# F405.net
KiCad netlist of a schematic drawn in Altium Designer
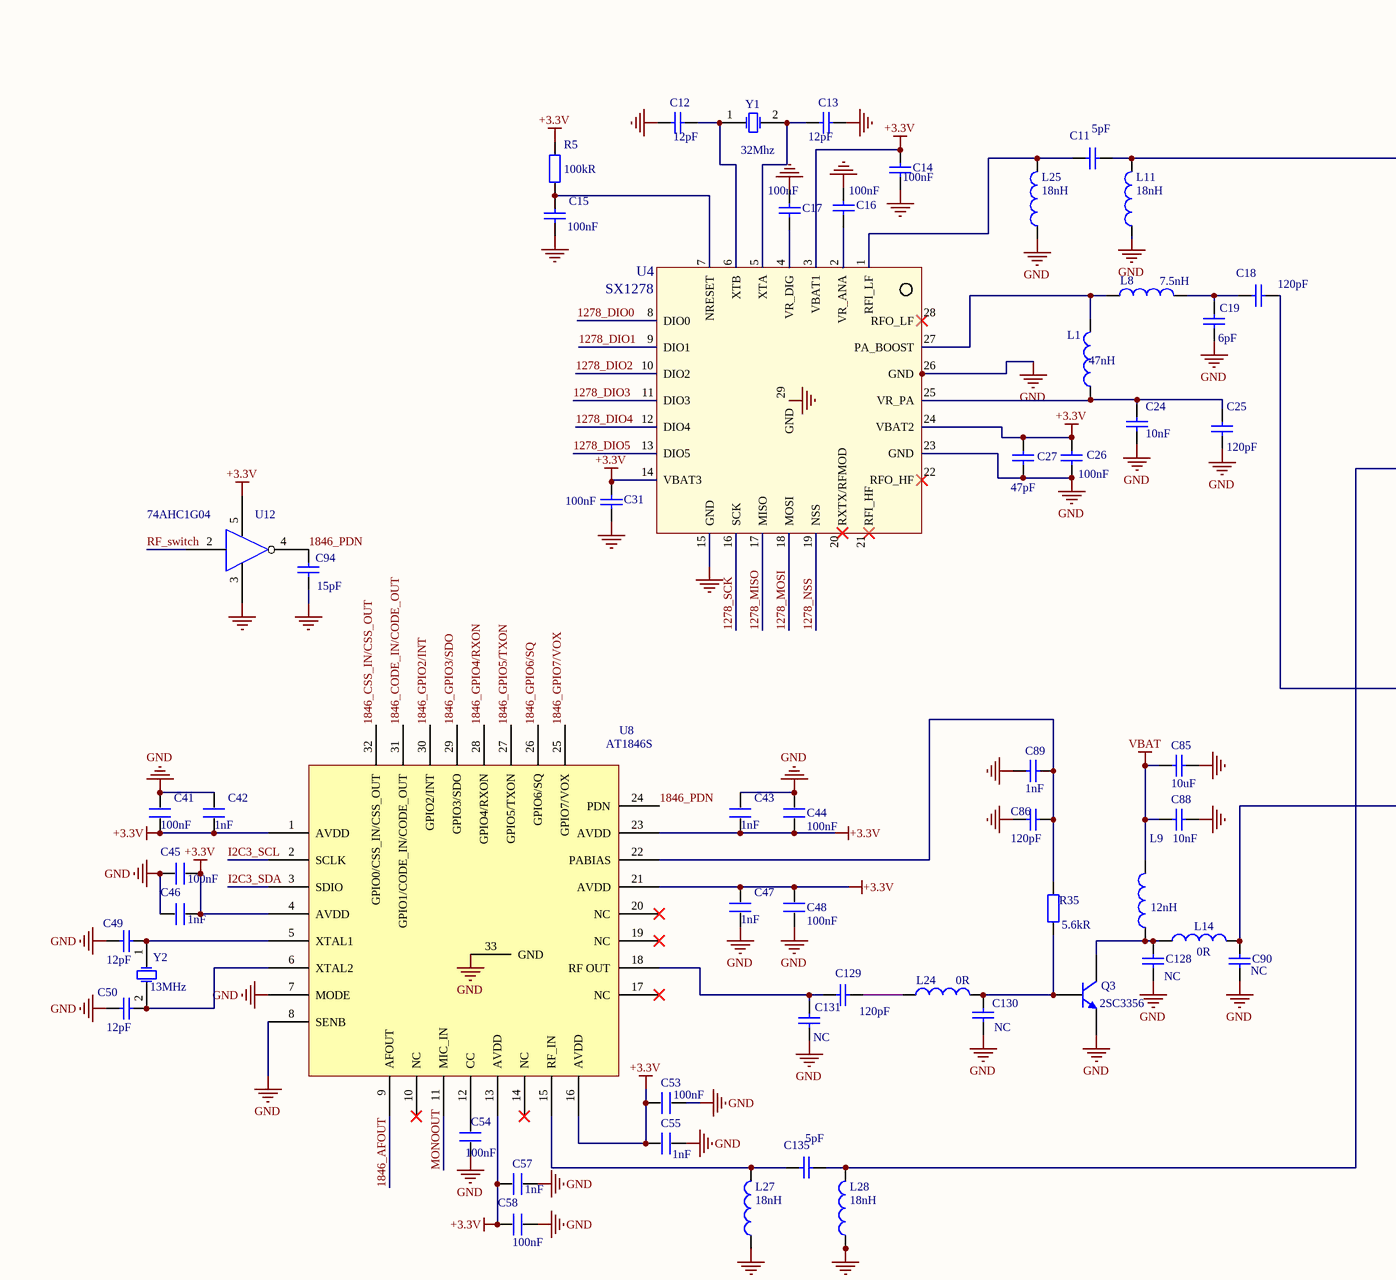
[diagram p0: F405.SchDoc, top left]
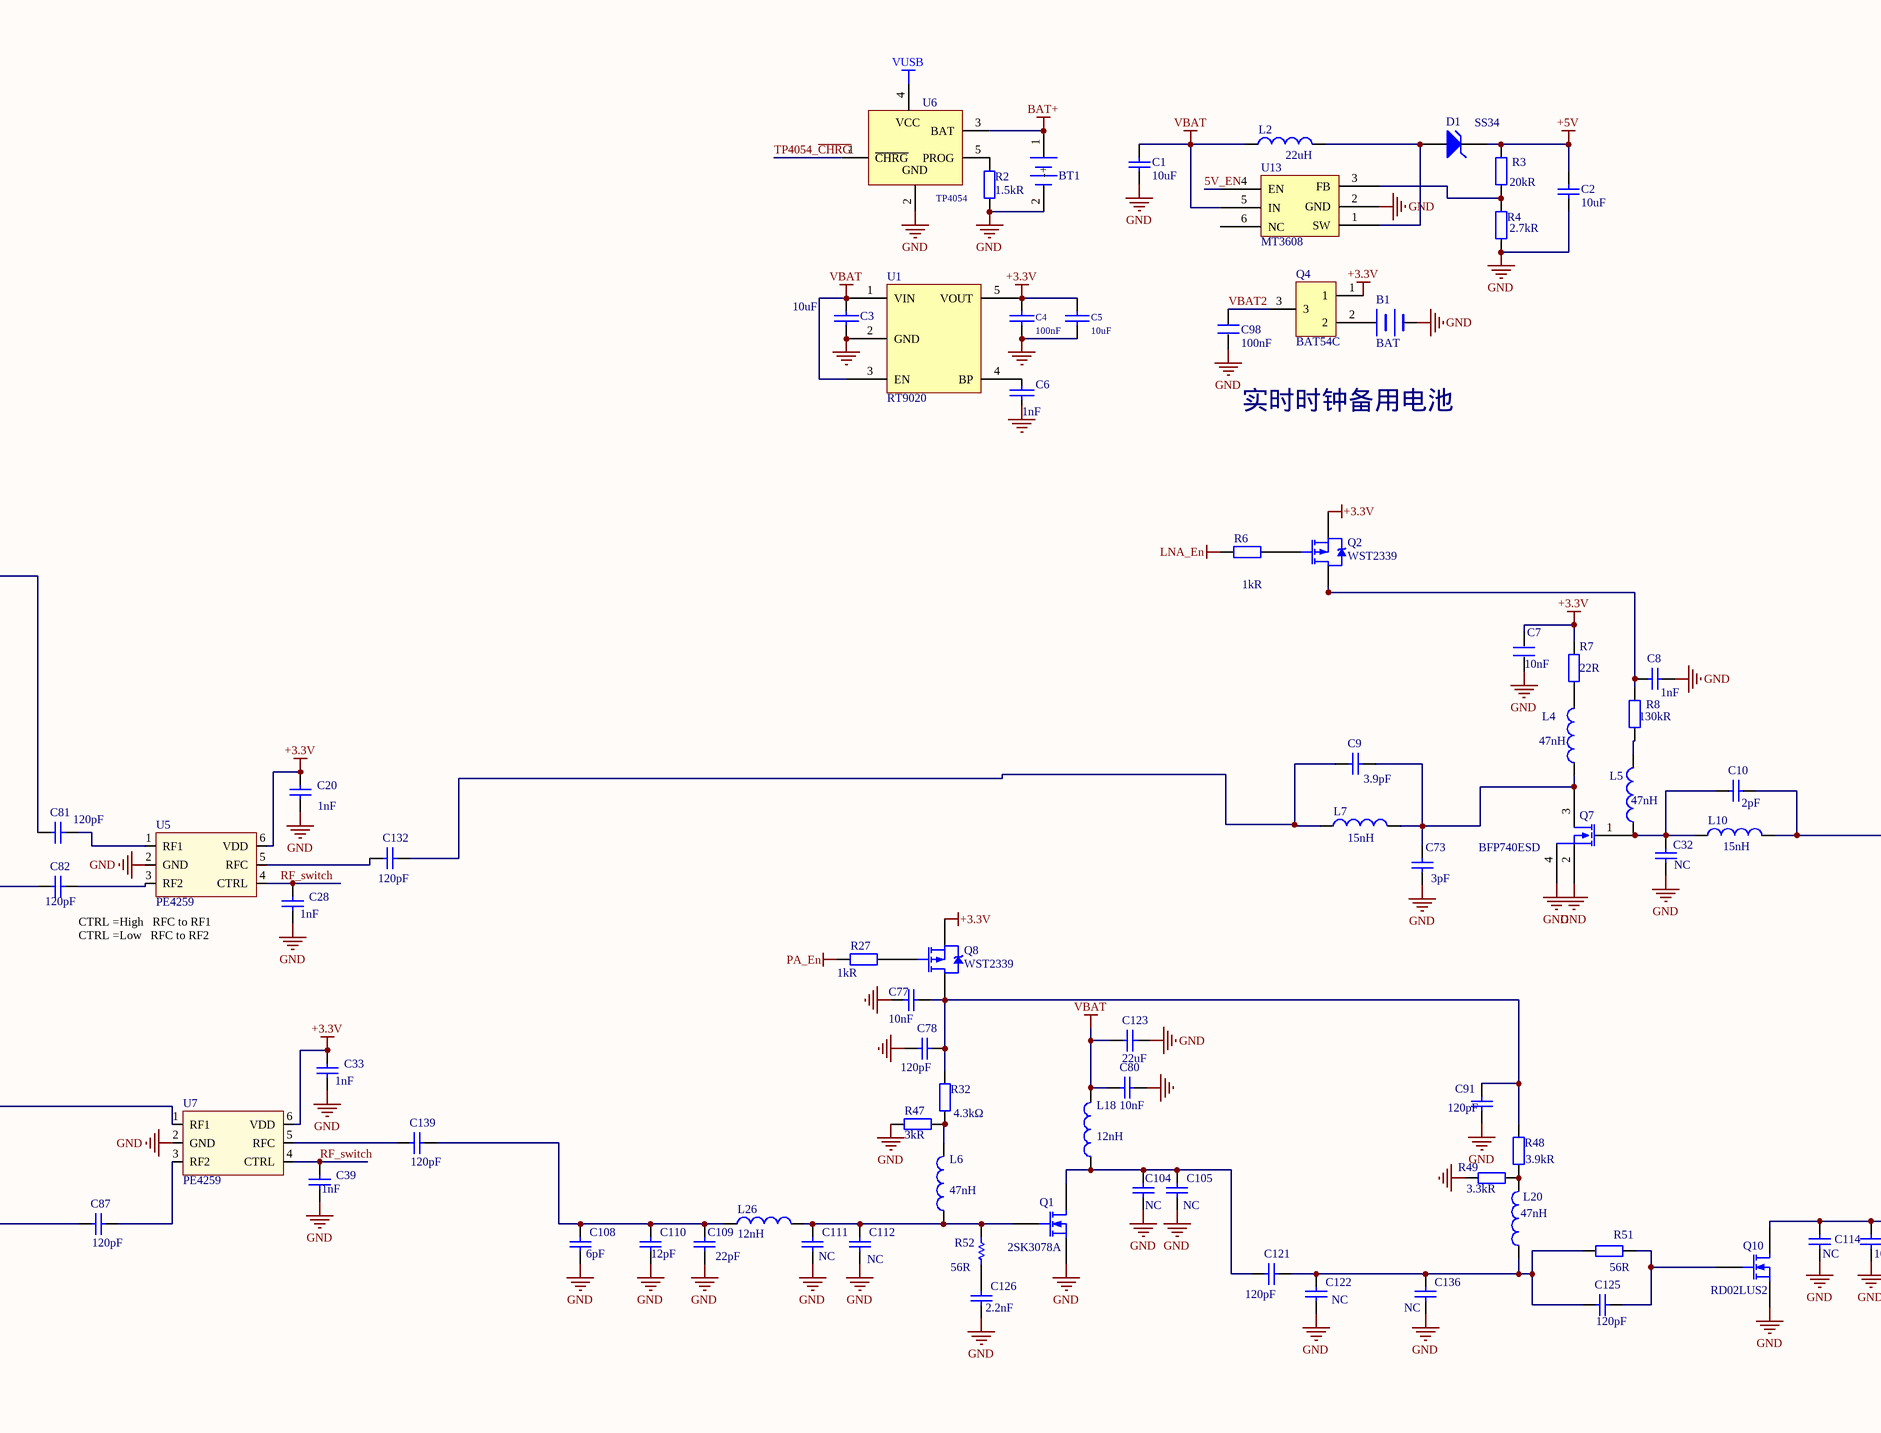
[diagram p1: F405.SchDoc, top middle]
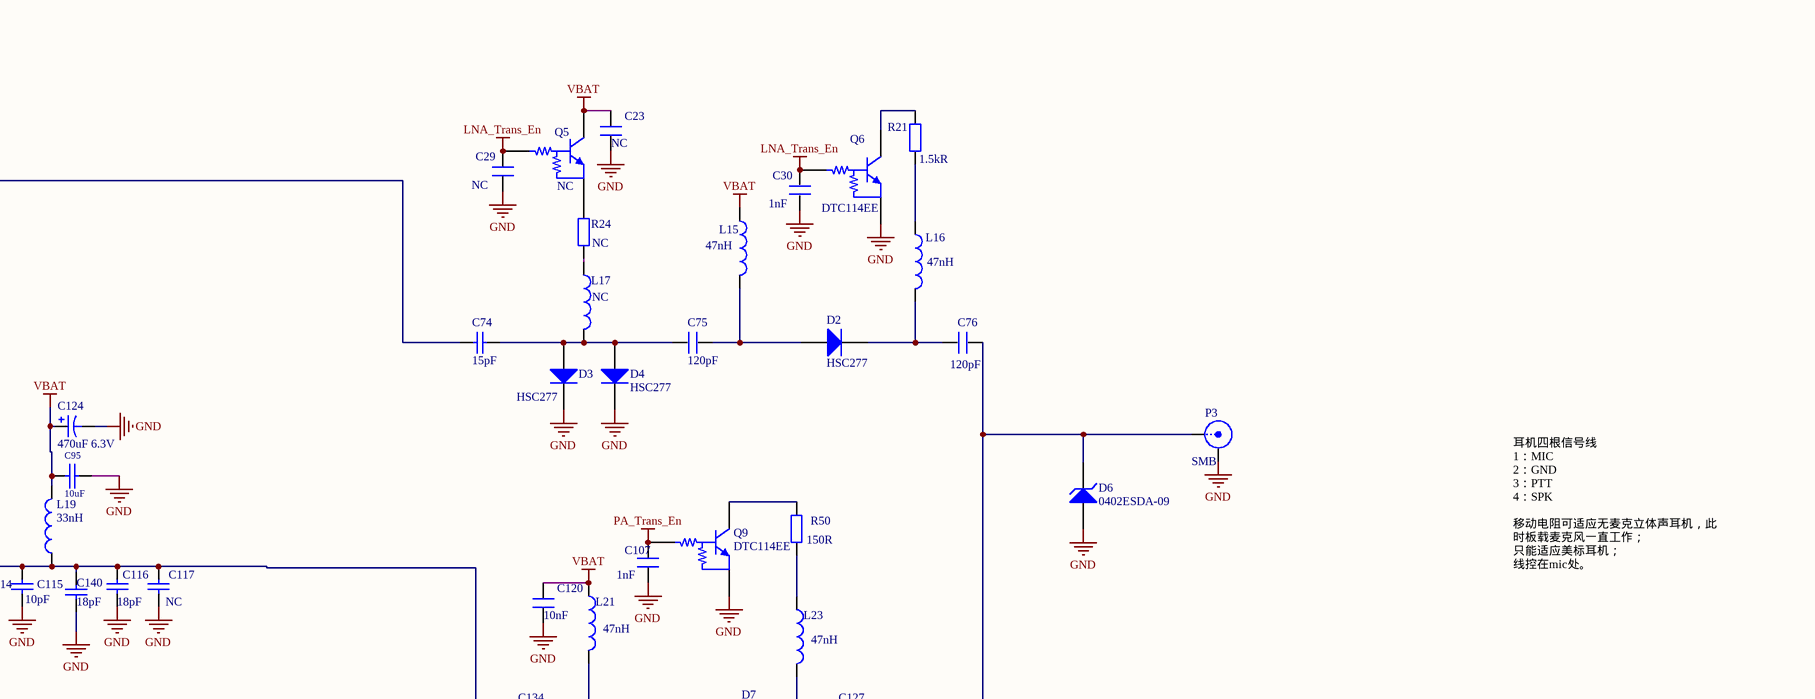
[diagram p2: F405.SchDoc, top right]
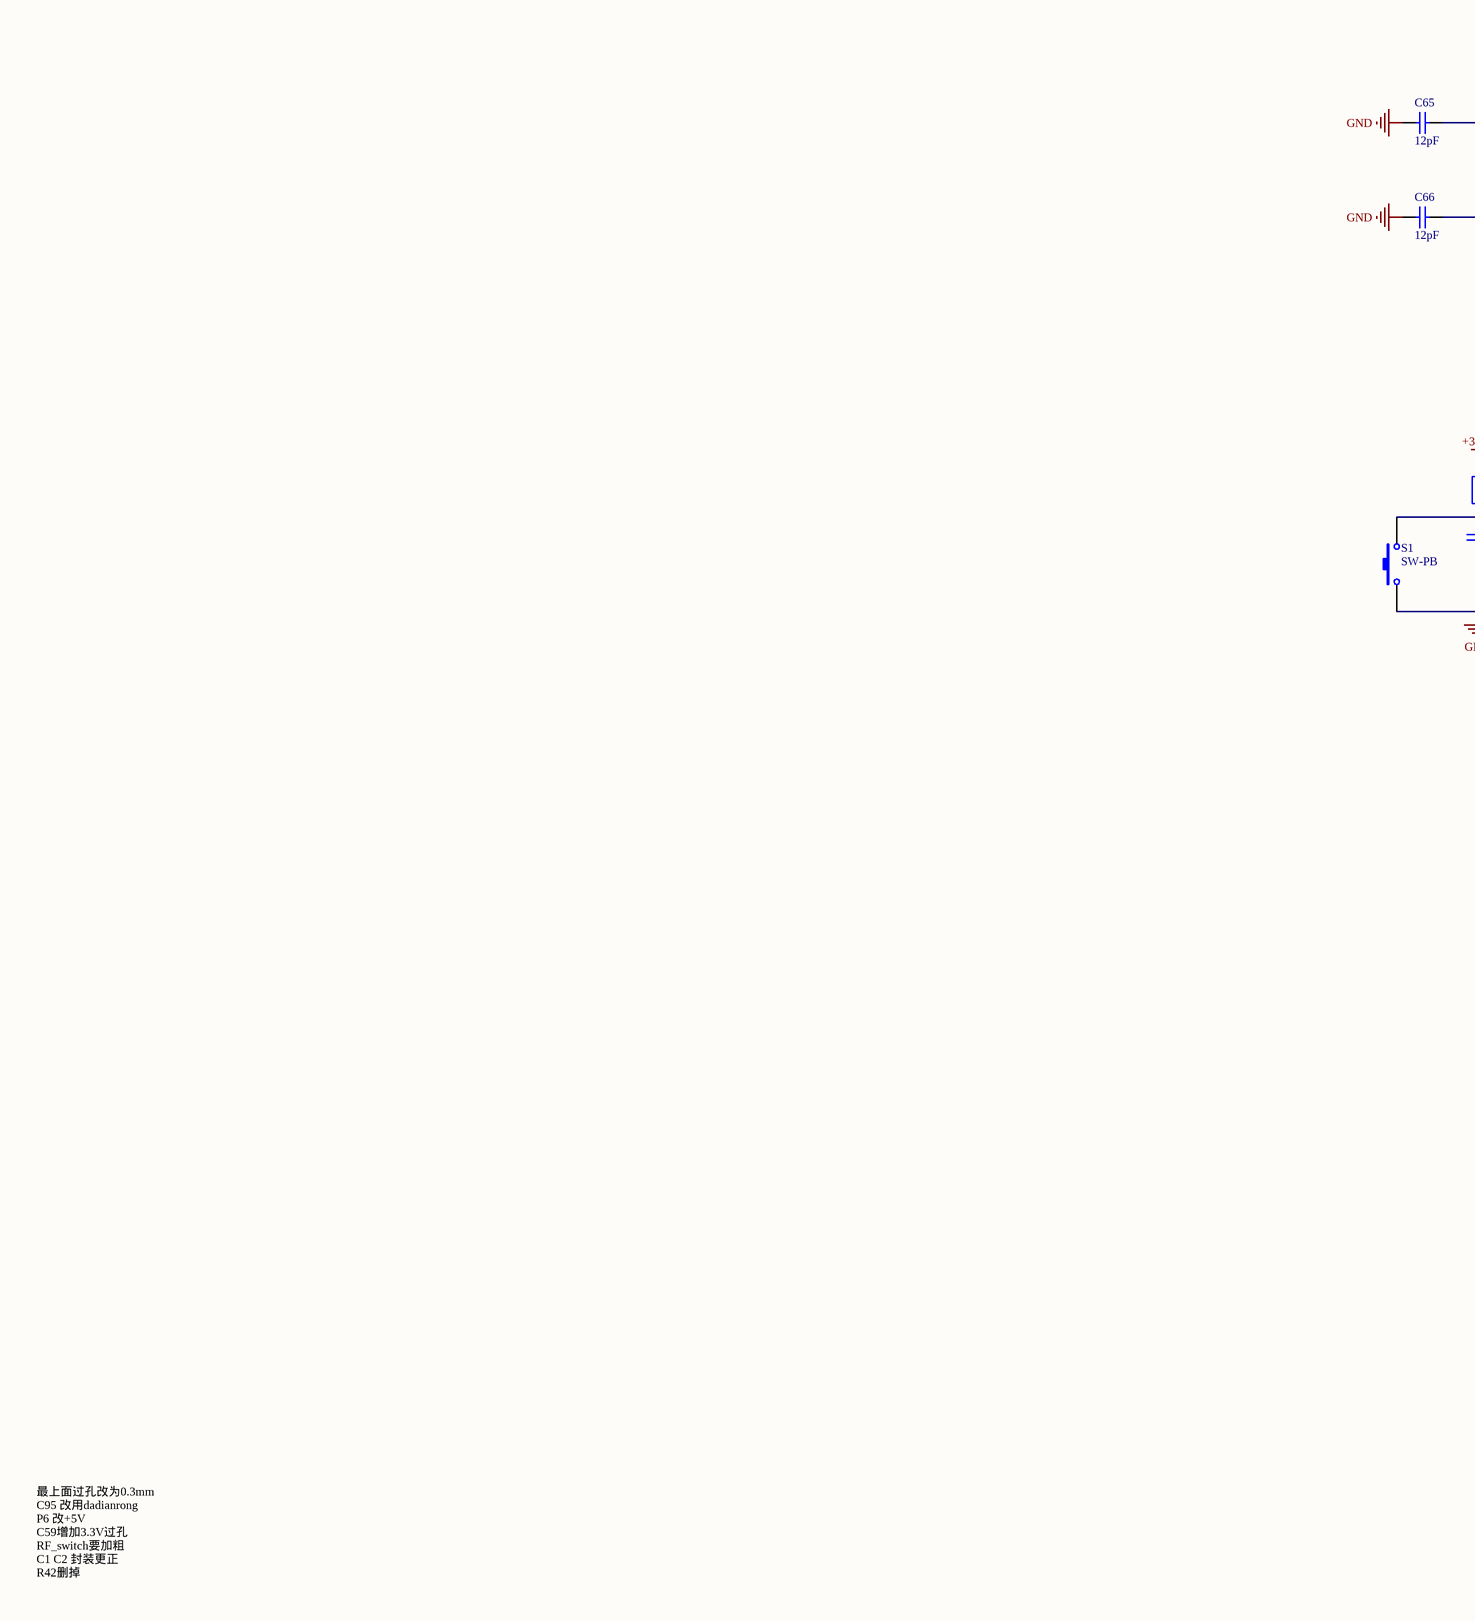
[diagram p3: F405.SchDoc, bottom left]
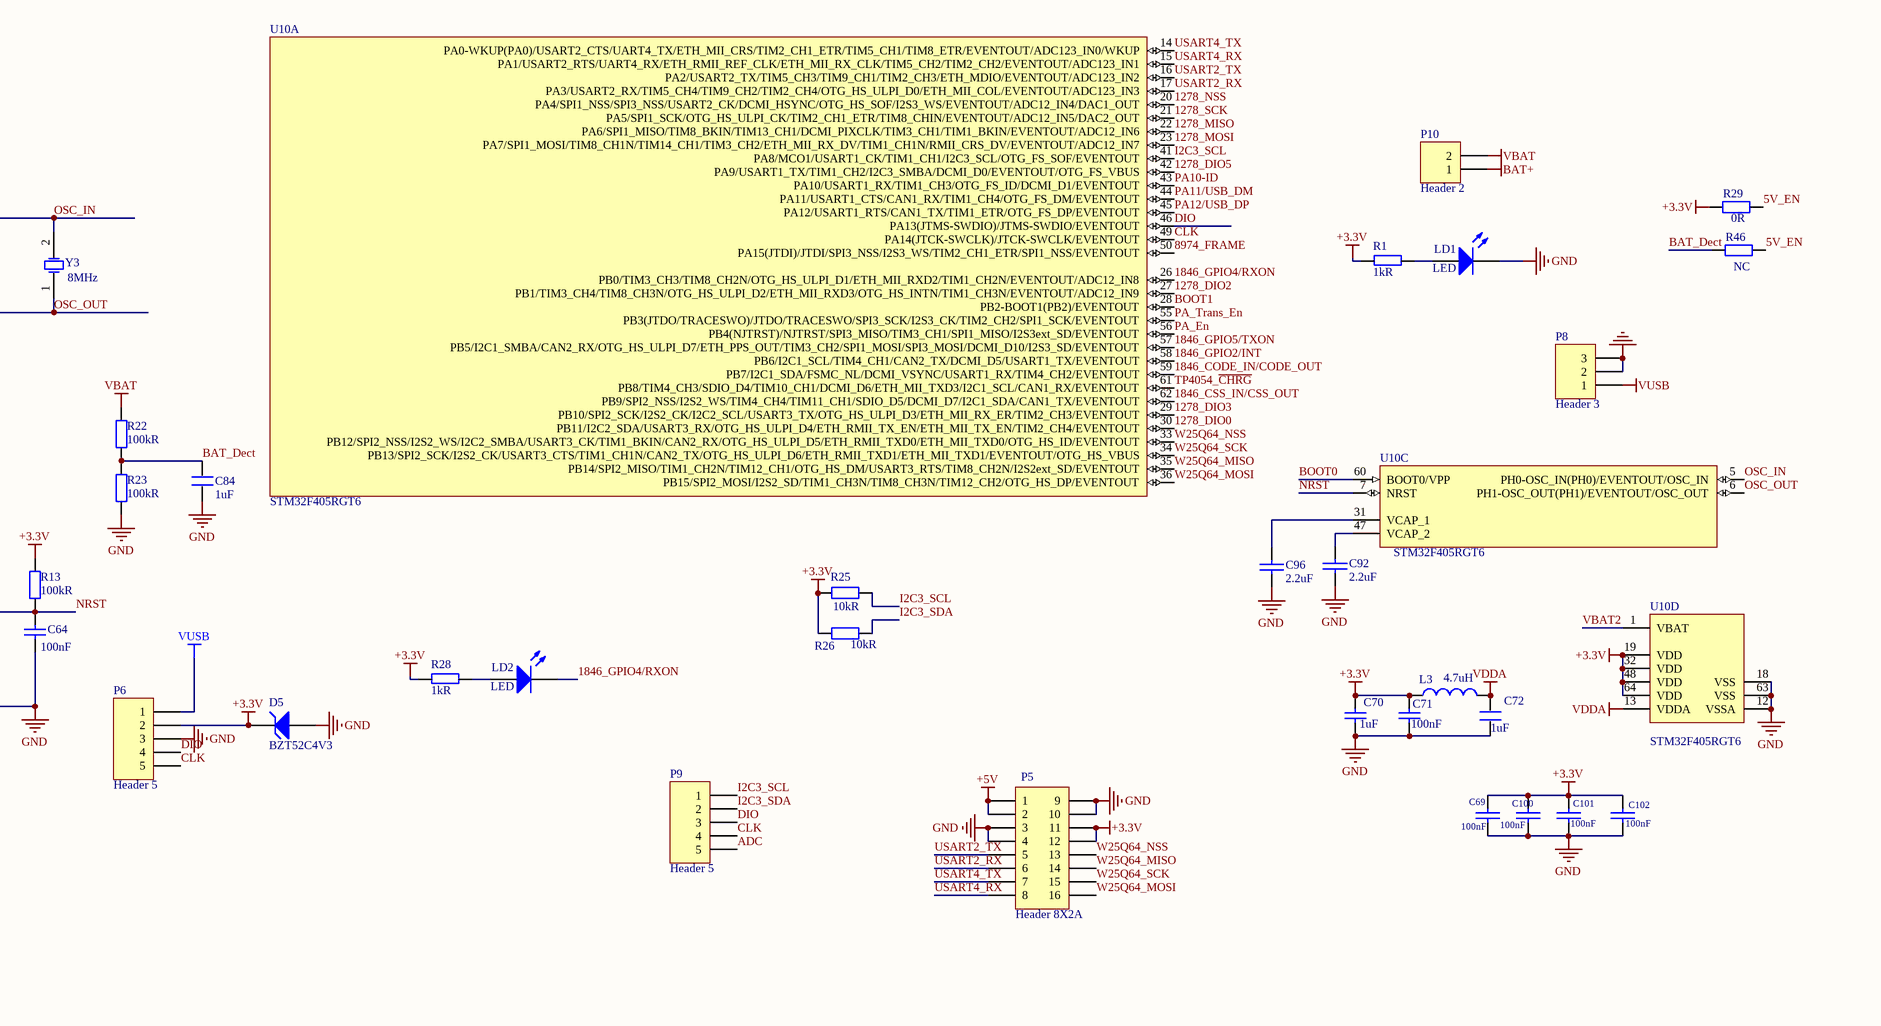
[diagram p4: F405.SchDoc, bottom middle]
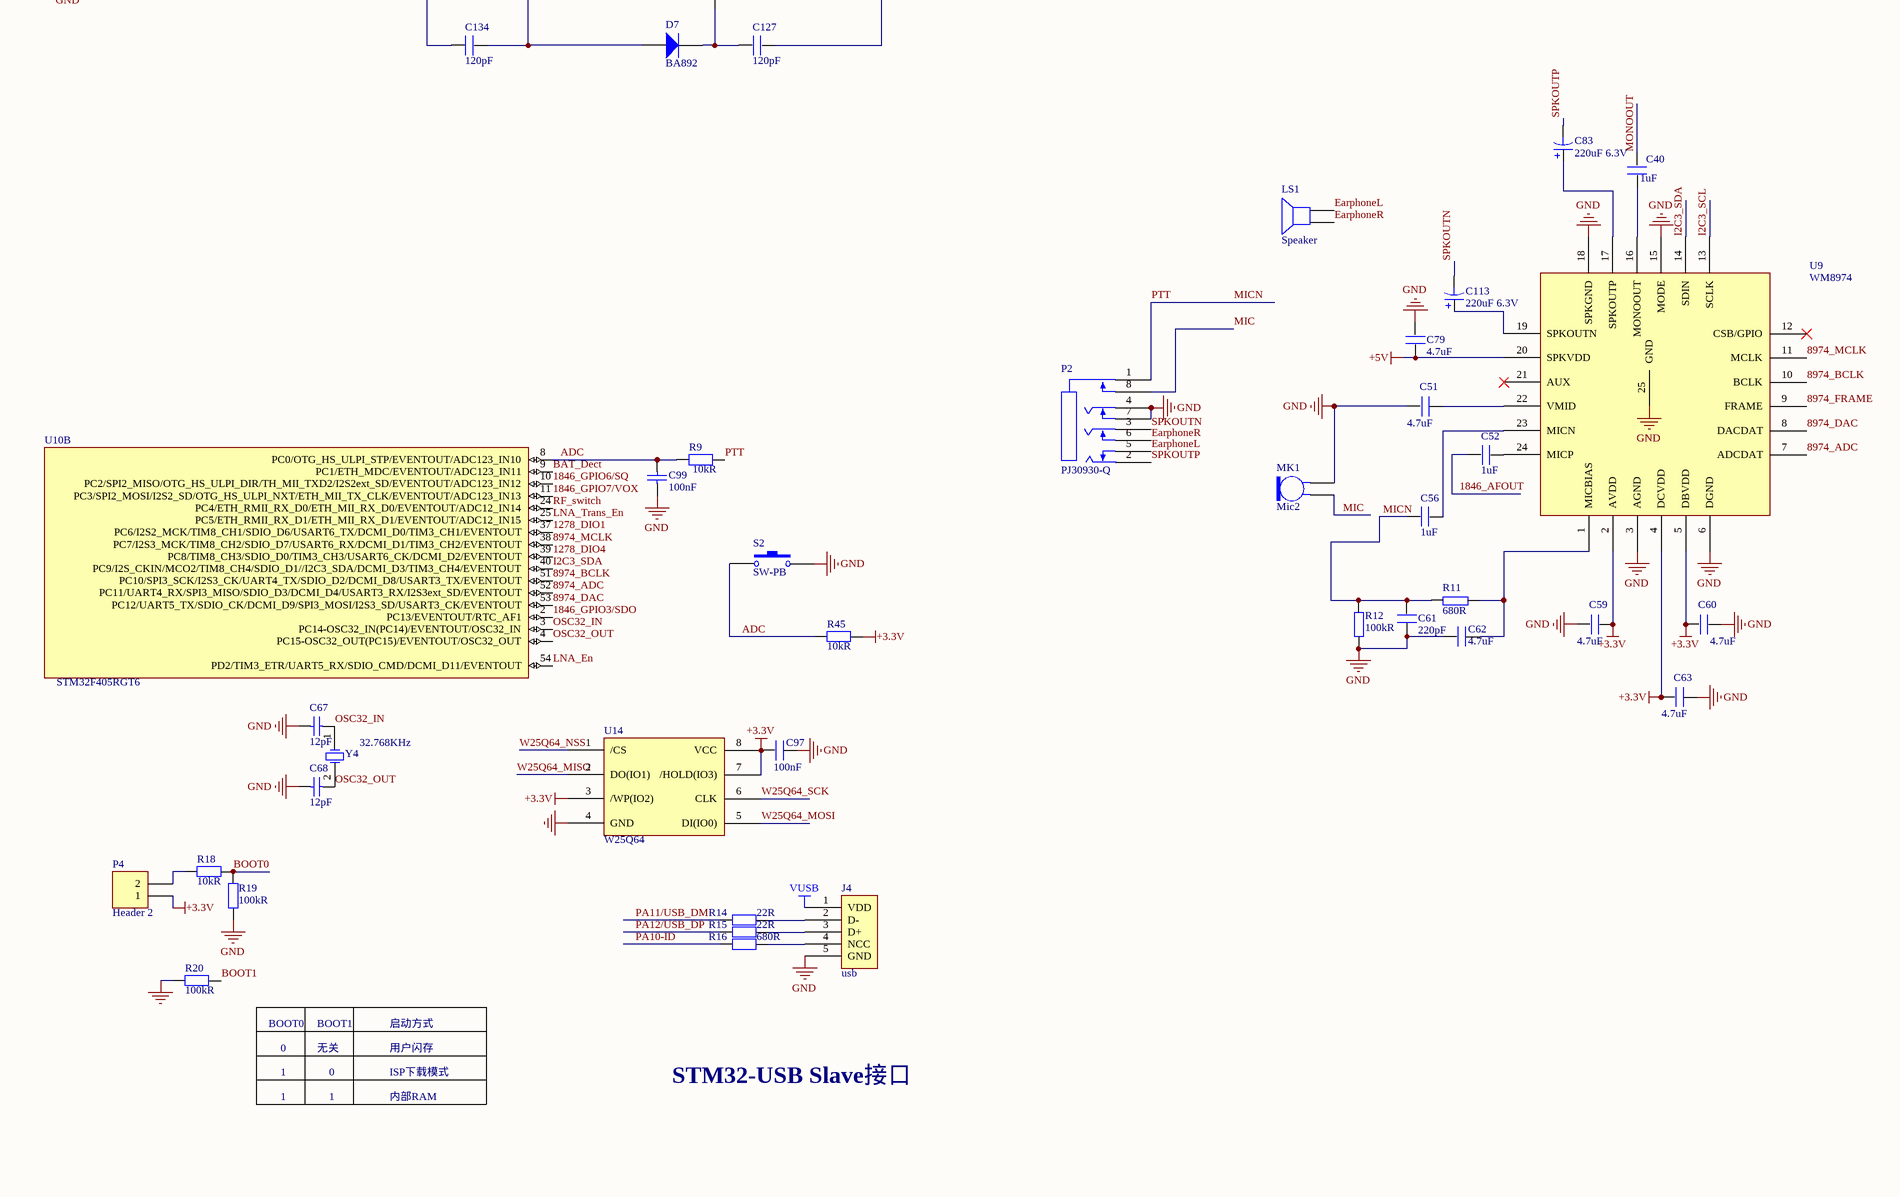
[diagram p5: F405.SchDoc, bottom right]

(export (version "E")
  (design (tool "Eeschema 10.0.6"))
  (components
    (comp (ref "B1") (value "BAT") (footprint "HDR1X2") (libsource (lib "*") (part "BATTERY")))
    (comp (ref "BT1")
      (value "纽扣电池座")
      (footprint "HDR1X2")
      (description "Multicell Battery")
      (fields (field (name "PUBLISHER") "Altium Limited"))
      (libsource (lib "MySchLib") (part "Battery"))
    )
    (comp (ref "C1")
      (value "10uF")
      (footprint "0603_C")
      (description "贴片电容")
      (fields (field (name "PUBLISHER") "Altium Limited"))
      (libsource (lib "SX1276_e268v01a") (part "Cap"))
    )
    (comp (ref "C2")
      (value "10uF")
      (footprint "0603_C")
      (description "贴片电容")
      (fields (field (name "PUBLISHER") "Altium Limited"))
      (libsource (lib "SX1276_e268v01a") (part "Cap"))
    )
    (comp (ref "C3")
      (value "10uF")
      (footprint "0402_C")
      (description "贴片电容")
      (libsource (lib "") (part "CAP_1"))
    )
    (comp (ref "C4")
      (value "100nF")
      (footprint "0402_C")
      (description "贴片电容")
      (libsource (lib "*") (part "CAP"))
    )
    (comp (ref "C5")
      (value "10uF")
      (footprint "0402_C")
      (description "贴片电容")
      (libsource (lib "*") (part "CAP"))
    )
    (comp (ref "C6")
      (value "1nF")
      (footprint "0402_C")
      (description "贴片电容")
      (libsource (lib "") (part "CAP_2"))
    )
    (comp (ref "C7")
      (value "10nF")
      (footprint "0402_C")
      (description "贴片电容")
      (libsource (lib "Emolib") (part "C_0603"))
    )
    (comp (ref "C8")
      (value "1nF")
      (footprint "0402_C")
      (description "贴片电容")
      (fields (field (name "PUBLISHER") "Altium Limited"))
      (libsource (lib "Miscellaneous Devices") (part "Cap"))
    )
    (comp (ref "C9")
      (value "3.9pF")
      (footprint "0402_C")
      (description "贴片电容")
      (fields (field (name "PUBLISHER") "Altium Limited"))
      (libsource (lib "SX1276_e268v01a") (part "Cap"))
    )
    (comp (ref "C10")
      (value "2pF")
      (footprint "0402_C")
      (description "贴片电容")
      (fields (field (name "PUBLISHER") "Altium Limited"))
      (libsource (lib "SX1276_e268v01a") (part "Cap"))
    )
    (comp (ref "C11")
      (value "5pF")
      (footprint "0402_C")
      (description "贴片电容")
      (fields (field (name "PUBLISHER") "Altium Limited"))
      (libsource (lib "SX1276_e268v01a") (part "Cap"))
    )
    (comp (ref "C12")
      (value "12pF")
      (footprint "0402_C")
      (description "贴片电容")
      (fields (field (name "PUBLISHER") "Altium Limited"))
      (libsource (lib "Miscellaneous Devices") (part "Cap"))
    )
    (comp (ref "C13")
      (value "12pF")
      (footprint "0402_C")
      (description "贴片电容")
      (fields (field (name "PUBLISHER") "Altium Limited"))
      (libsource (lib "Miscellaneous Devices") (part "Cap"))
    )
    (comp (ref "C14")
      (value "100nF")
      (footprint "0402_C")
      (description "贴片电容")
      (fields (field (name "PUBLISHER") "Altium Limited"))
      (libsource (lib "Miscellaneous Devices") (part "Cap"))
    )
    (comp (ref "C15")
      (value "100nF")
      (footprint "0402_C")
      (description "贴片电容")
      (fields (field (name "PUBLISHER") "Altium Limited"))
      (libsource (lib "Miscellaneous Devices") (part "Cap"))
    )
    (comp (ref "C16")
      (value "100nF")
      (footprint "0402_C")
      (description "贴片电容")
      (fields (field (name "PUBLISHER") "Altium Limited"))
      (libsource (lib "Miscellaneous Devices") (part "Cap"))
    )
    (comp (ref "C17")
      (value "100nF")
      (footprint "0402_C")
      (description "贴片电容")
      (fields (field (name "PUBLISHER") "Altium Limited"))
      (libsource (lib "Miscellaneous Devices") (part "Cap"))
    )
    (comp (ref "C18")
      (value "120pF")
      (footprint "0402_C")
      (description "贴片电容")
      (fields (field (name "PUBLISHER") "Altium Limited"))
      (libsource (lib "SX1276_e268v01a") (part "Cap"))
    )
    (comp (ref "C19")
      (value "6pF")
      (footprint "0402_C")
      (description "贴片电容")
      (fields (field (name "PUBLISHER") "Altium Limited"))
      (libsource (lib "SX1276_e268v01a") (part "Cap"))
    )
    (comp (ref "C20")
      (value "1nF")
      (footprint "0402_C")
      (description "贴片电容")
      (fields (field (name "PUBLISHER") "Altium Limited"))
      (libsource (lib "SX1276_e268v01a") (part "Cap"))
    )
    (comp (ref "C23")
      (value "NC")
      (footprint "0402_C")
      (description "贴片电容")
      (libsource (lib "Emolib") (part "C_0603"))
    )
    (comp (ref "C24")
      (value "10nF")
      (footprint "0402_C")
      (description "贴片电容")
      (fields (field (name "PUBLISHER") "Altium Limited"))
      (libsource (lib "SX1276_e268v01a") (part "Cap"))
    )
    (comp (ref "C25")
      (value "120pF")
      (footprint "0402_C")
      (description "贴片电容")
      (fields (field (name "PUBLISHER") "Altium Limited"))
      (libsource (lib "SX1276_e268v01a") (part "Cap"))
    )
    (comp (ref "C26")
      (value "100nF")
      (footprint "0402_C")
      (description "贴片电容")
      (fields (field (name "PUBLISHER") "Altium Limited"))
      (libsource (lib "SX1276_e268v01a") (part "Cap"))
    )
    (comp (ref "C27")
      (value "47pF")
      (footprint "0402_C")
      (description "贴片电容")
      (fields (field (name "PUBLISHER") "Altium Limited"))
      (libsource (lib "SX1276_e268v01a") (part "Cap"))
    )
    (comp (ref "C28")
      (value "1nF")
      (footprint "0402_C")
      (description "贴片电容")
      (fields (field (name "PUBLISHER") "Altium Limited"))
      (libsource (lib "SX1276_e268v01a") (part "Cap"))
    )
    (comp (ref "C29")
      (value "NC")
      (footprint "0402_C")
      (description "贴片电容")
      (libsource (lib "Emolib") (part "C_0603"))
    )
    (comp (ref "C30")
      (value "1nF")
      (footprint "0402_C")
      (description "贴片电容")
      (libsource (lib "Emolib") (part "C_0603"))
    )
    (comp (ref "C31")
      (value "100nF")
      (footprint "0402_C")
      (description "贴片电容")
      (fields (field (name "PUBLISHER") "Altium Limited"))
      (libsource (lib "Miscellaneous Devices") (part "Cap"))
    )
    (comp (ref "C32")
      (value "NC")
      (footprint "0402_C")
      (description "贴片电容")
      (fields (field (name "PUBLISHER") "Altium Limited"))
      (libsource (lib "SX1276_e268v01a") (part "Cap"))
    )
    (comp (ref "C33")
      (value "1nF")
      (footprint "0402_C")
      (description "贴片电容")
      (fields (field (name "PUBLISHER") "Altium Limited"))
      (libsource (lib "SX1276_e268v01a") (part "Cap"))
    )
    (comp (ref "C39")
      (value "1nF")
      (footprint "0402_C")
      (description "贴片电容")
      (fields (field (name "PUBLISHER") "Altium Limited"))
      (libsource (lib "SX1276_e268v01a") (part "Cap"))
    )
    (comp (ref "C40")
      (value "1uF")
      (footprint "0402_C")
      (description "贴片电容")
      (libsource (lib "Emolib") (part "C_0603"))
    )
    (comp (ref "C41")
      (value "100nF")
      (footprint "0402_C")
      (description "贴片电容")
      (libsource (lib "Emolib") (part "C_0603"))
    )
    (comp (ref "C42")
      (value "1nF")
      (footprint "0402_C")
      (description "贴片电容")
      (libsource (lib "Emolib") (part "C_0603"))
    )
    (comp (ref "C43")
      (value "1nF")
      (footprint "0402_C")
      (description "贴片电容")
      (libsource (lib "Emolib") (part "C_0603"))
    )
    (comp (ref "C44")
      (value "100nF")
      (footprint "0402_C")
      (description "贴片电容")
      (libsource (lib "Emolib") (part "C_0603"))
    )
    (comp (ref "C45")
      (value "100nF")
      (footprint "0402_C")
      (description "贴片电容")
      (libsource (lib "Emolib") (part "C_0603"))
    )
    (comp (ref "C46")
      (value "1nF")
      (footprint "0402_C")
      (description "贴片电容")
      (libsource (lib "Emolib") (part "C_0603"))
    )
    (comp (ref "C47")
      (value "1nF")
      (footprint "0402_C")
      (description "贴片电容")
      (libsource (lib "Emolib") (part "C_0603"))
    )
    (comp (ref "C48")
      (value "100nF")
      (footprint "0402_C")
      (description "贴片电容")
      (libsource (lib "Emolib") (part "C_0603"))
    )
    (comp (ref "C49")
      (value "12pF")
      (footprint "0402_C")
      (description "贴片电容")
      (fields (field (name "PUBLISHER") "Altium Limited"))
      (libsource (lib "Miscellaneous Devices") (part "Cap Semi"))
    )
    (comp (ref "C50")
      (value "12pF")
      (footprint "0402_C")
      (description "贴片电容")
      (fields (field (name "PUBLISHER") "Altium Limited"))
      (libsource (lib "Miscellaneous Devices") (part "Cap Semi"))
    )
    (comp (ref "C51")
      (value "4.7uF")
      (footprint "0402_C")
      (description "贴片电容")
      (libsource (lib "Emolib") (part "C_0603"))
    )
    (comp (ref "C52")
      (value "1uF")
      (footprint "0402_C")
      (description "贴片电容")
      (libsource (lib "Emolib") (part "C_0603"))
    )
    (comp (ref "C53")
      (value "100nF")
      (footprint "0402_C")
      (description "贴片电容")
      (libsource (lib "Emolib") (part "C_0603"))
    )
    (comp (ref "C54")
      (value "100nF")
      (footprint "0402_C")
      (description "贴片电容")
      (libsource (lib "Emolib") (part "C_0603"))
    )
    (comp (ref "C55")
      (value "1nF")
      (footprint "0402_C")
      (description "贴片电容")
      (libsource (lib "Emolib") (part "C_0603"))
    )
    (comp (ref "C56")
      (value "1uF")
      (footprint "0402_C")
      (description "贴片电容")
      (libsource (lib "Emolib") (part "C_0603"))
    )
    (comp (ref "C57")
      (value "1nF")
      (footprint "0402_C")
      (description "贴片电容")
      (libsource (lib "Emolib") (part "C_0603"))
    )
    (comp (ref "C58")
      (value "100nF")
      (footprint "0402_C")
      (description "贴片电容")
      (libsource (lib "Emolib") (part "C_0603"))
    )
    (comp (ref "C59")
      (value "4.7uF")
      (footprint "0402_C")
      (description "贴片电容")
      (libsource (lib "Emolib") (part "C_0603"))
    )
    (comp (ref "C60")
      (value "4.7uF")
      (footprint "0402_C")
      (description "贴片电容")
      (libsource (lib "Emolib") (part "C_0603"))
    )
    (comp (ref "C61")
      (value "220pF")
      (footprint "0402_C")
      (description "贴片电容")
      (libsource (lib "Emolib") (part "C_0603"))
    )
    (comp (ref "C62")
      (value "4.7uF")
      (footprint "0402_C")
      (description "贴片电容")
      (libsource (lib "Emolib") (part "C_0603"))
    )
    (comp (ref "C63")
      (value "4.7uF")
      (footprint "0402_C")
      (description "贴片电容")
      (libsource (lib "Emolib") (part "C_0603"))
    )
    (comp (ref "C64")
      (value "100nF")
      (footprint "0402_C")
      (description "贴片电容")
      (fields (field (name "PUBLISHER") "Altium Limited"))
      (libsource (lib "Miscellaneous Devices") (part "Cap Semi"))
    )
    (comp (ref "C65")
      (value "12pF")
      (footprint "0402_C")
      (description "贴片电容")
      (fields (field (name "PUBLISHER") "Altium Limited"))
      (libsource (lib "Miscellaneous Devices") (part "Cap Semi"))
    )
    (comp (ref "C66")
      (value "12pF")
      (footprint "0402_C")
      (description "贴片电容")
      (fields (field (name "PUBLISHER") "Altium Limited"))
      (libsource (lib "Miscellaneous Devices") (part "Cap Semi"))
    )
    (comp (ref "C67")
      (value "12pF")
      (footprint "0402_C")
      (description "贴片电容")
      (fields (field (name "PUBLISHER") "Altium Limited"))
      (libsource (lib "Miscellaneous Devices") (part "Cap Semi"))
    )
    (comp (ref "C68")
      (value "12pF")
      (footprint "0402_C")
      (description "贴片电容")
      (fields (field (name "PUBLISHER") "Altium Limited"))
      (libsource (lib "Miscellaneous Devices") (part "Cap Semi"))
    )
    (comp (ref "C69")
      (value "100nF")
      (footprint "0402_C")
      (description "Capacitor")
      (libsource (lib "*") (part "CAP"))
    )
    (comp (ref "C70")
      (value "1uF")
      (footprint "0402_C")
      (description "贴片电容")
      (fields (field (name "PUBLISHER") "Altium Limited"))
      (libsource (lib "Miscellaneous Devices") (part "Cap Semi"))
    )
    (comp (ref "C71")
      (value "100nF")
      (footprint "0402_C")
      (description "贴片电容")
      (fields (field (name "PUBLISHER") "Altium Limited"))
      (libsource (lib "Miscellaneous Devices") (part "Cap Semi"))
    )
    (comp (ref "C72")
      (value "1uF")
      (footprint "0402_C")
      (description "贴片电容")
      (libsource (lib "Emolib") (part "C_0603"))
    )
    (comp (ref "C73")
      (value "3pF")
      (footprint "0402_C")
      (description "贴片电容")
      (fields (field (name "PUBLISHER") "Altium Limited"))
      (libsource (lib "SX1276_e268v01a") (part "Cap"))
    )
    (comp (ref "C74")
      (value "15pF")
      (footprint "0402_C")
      (description "贴片电容")
      (fields (field (name "PUBLISHER") "Altium Limited"))
      (libsource (lib "SX1276_e268v01a") (part "Cap"))
    )
    (comp (ref "C75")
      (value "120pF")
      (footprint "0402_C")
      (description "贴片电容")
      (libsource (lib "Emolib") (part "C_0603"))
    )
    (comp (ref "C76")
      (value "120pF")
      (footprint "0402_C")
      (description "贴片电容")
      (libsource (lib "Emolib") (part "C_0603"))
    )
    (comp (ref "C77")
      (value "10nF")
      (footprint "0402_C")
      (description "贴片电容")
      (fields (field (name "PUBLISHER") "Altium Limited"))
      (libsource (lib "Miscellaneous Devices") (part "Cap"))
    )
    (comp (ref "C78")
      (value "120pF")
      (footprint "0402_C")
      (description "贴片电容")
      (fields (field (name "PUBLISHER") "Altium Limited"))
      (libsource (lib "Miscellaneous Devices") (part "Cap"))
    )
    (comp (ref "C79")
      (value "4.7uF")
      (footprint "0402_C")
      (description "贴片电容")
      (libsource (lib "Emolib") (part "C_0603"))
    )
    (comp (ref "C80")
      (value "10nF")
      (footprint "0402_C")
      (description "贴片电容")
      (fields (field (name "PUBLISHER") "Altium Limited"))
      (libsource (lib "Miscellaneous Devices") (part "Cap"))
    )
    (comp (ref "C81")
      (value "120pF")
      (footprint "0402_C")
      (description "贴片电容")
      (fields (field (name "PUBLISHER") "Altium Limited"))
      (libsource (lib "SX1276_e268v01a") (part "Cap"))
    )
    (comp (ref "C82")
      (value "120pF")
      (footprint "0402_C")
      (description "贴片电容")
      (fields (field (name "PUBLISHER") "Altium Limited"))
      (libsource (lib "SX1276_e268v01a") (part "Cap"))
    )
    (comp (ref "C83")
      (value "220uF 6.3V")
      (footprint "CASE-B_3528")
      (description "钽电容")
      (fields (field (name "PUBLISHER") "Altium Limited"))
      (libsource (lib "Miscellaneous Devices") (part "Cap Pol1"))
    )
    (comp (ref "C84")
      (value "1uF")
      (footprint "0402_C")
      (description "贴片电容")
      (libsource (lib "Emolib") (part "C_0603"))
    )
    (comp (ref "C85")
      (value "10uF")
      (footprint "0402_C")
      (description "贴片电容")
      (fields (field (name "PUBLISHER") "Altium Limited"))
      (libsource (lib "Miscellaneous Devices") (part "Cap"))
    )
    (comp (ref "C86")
      (value "120pF")
      (footprint "0402_C")
      (description "贴片电容")
      (fields (field (name "PUBLISHER") "Altium Limited"))
      (libsource (lib "Miscellaneous Devices") (part "Cap"))
    )
    (comp (ref "C87")
      (value "120pF")
      (footprint "0402_C")
      (description "贴片电容")
      (fields (field (name "PUBLISHER") "Altium Limited"))
      (libsource (lib "SX1276_e268v01a") (part "Cap"))
    )
    (comp (ref "C88")
      (value "10nF")
      (footprint "0402_C")
      (description "贴片电容")
      (fields (field (name "PUBLISHER") "Altium Limited"))
      (libsource (lib "Miscellaneous Devices") (part "Cap"))
    )
    (comp (ref "C89")
      (value "1nF")
      (footprint "0402_C")
      (description "贴片电容")
      (fields (field (name "PUBLISHER") "Altium Limited"))
      (libsource (lib "Miscellaneous Devices") (part "Cap"))
    )
    (comp (ref "C90")
      (value "NC")
      (footprint "0402_C")
      (description "贴片电容")
      (fields (field (name "PUBLISHER") "Altium Limited"))
      (libsource (lib "SX1276_e268v01a") (part "Cap"))
    )
    (comp (ref "C91")
      (value "120pF")
      (footprint "0402_C")
      (description "Capacitor")
      (fields (field (name "PUBLISHER") "Altium Limited"))
      (libsource (lib "Miscellaneous Devices") (part "Cap"))
    )
    (comp (ref "C92")
      (value "2.2uF")
      (footprint "0402_C")
      (description "贴片电容")
      (libsource (lib "*") (part "CAP"))
    )
    (comp (ref "C94")
      (value "15pF")
      (footprint "0402_C")
      (description "贴片电容")
      (fields (field (name "PUBLISHER") "Altium Limited"))
      (libsource (lib "SX1276_e268v01a") (part "Cap"))
    )
    (comp (ref "C95")
      (value "10uF")
      (footprint "0603_C")
      (description "贴片电容")
      (libsource (lib "*") (part "CAP"))
    )
    (comp (ref "C96")
      (value "2.2uF")
      (footprint "0402_C")
      (description "贴片电容")
      (libsource (lib "*") (part "CAP"))
    )
    (comp (ref "C97")
      (value "100nF")
      (footprint "0402_C")
      (description "贴片电容")
      (libsource (lib "Emolib") (part "C_0603"))
    )
    (comp (ref "C98")
      (value "100nF")
      (footprint "0402_C")
      (description "贴片电容")
      (libsource (lib "Emolib") (part "C_0603"))
    )
    (comp (ref "C99")
      (value "100nF")
      (footprint "0402_C")
      (description "贴片电容")
      (fields (field (name "PUBLISHER") "Altium Limited"))
      (libsource (lib "Miscellaneous Devices") (part "Cap Semi"))
    )
    (comp (ref "C100")
      (value "100nF")
      (footprint "0402_C")
      (description "贴片电容")
      (libsource (lib "*") (part "CAP"))
    )
    (comp (ref "C101")
      (value "100nF")
      (footprint "0402_C")
      (description "贴片电容")
      (libsource (lib "*") (part "CAP"))
    )
    (comp (ref "C102")
      (value "100nF")
      (footprint "0402_C")
      (description "贴片电容")
      (libsource (lib "*") (part "CAP"))
    )
    (comp (ref "C104")
      (value "NC")
      (footprint "0402_C")
      (description "贴片电容")
      (fields (field (name "PUBLISHER") "Altium Limited"))
      (libsource (lib "SX1276_e268v01a") (part "Cap"))
    )
    (comp (ref "C105")
      (value "NC")
      (footprint "0402_C")
      (description "贴片电容")
      (fields (field (name "PUBLISHER") "Altium Limited"))
      (libsource (lib "SX1276_e268v01a") (part "Cap"))
    )
    (comp (ref "C107")
      (value "1nF")
      (footprint "0402_C")
      (description "贴片电容")
      (libsource (lib "Emolib") (part "C_0603"))
    )
    (comp (ref "C108")
      (value "6pF")
      (footprint "0402_C")
      (description "贴片电容")
      (fields (field (name "PUBLISHER") "Altium Limited"))
      (libsource (lib "SX1276_e268v01a") (part "Cap"))
    )
    (comp (ref "C109")
      (value "22pF")
      (footprint "0402_C")
      (description "贴片电容")
      (fields (field (name "PUBLISHER") "Altium Limited"))
      (libsource (lib "SX1276_e268v01a") (part "Cap"))
    )
    (comp (ref "C110")
      (value "12pF")
      (footprint "0402_C")
      (description "贴片电容")
      (fields (field (name "PUBLISHER") "Altium Limited"))
      (libsource (lib "SX1276_e268v01a") (part "Cap"))
    )
    (comp (ref "C111")
      (value "NC")
      (footprint "0402_C")
      (description "贴片电容")
      (fields (field (name "PUBLISHER") "Altium Limited"))
      (libsource (lib "SX1276_e268v01a") (part "Cap"))
    )
    (comp (ref "C112")
      (value "NC")
      (footprint "0402_C")
      (description "贴片电容")
      (fields (field (name "PUBLISHER") "Altium Limited"))
      (libsource (lib "SX1276_e268v01a") (part "Cap"))
    )
    (comp (ref "C113")
      (value "220uF 6.3V")
      (footprint "CASE-B_3528")
      (description "钽电容")
      (fields (field (name "PUBLISHER") "Altium Limited"))
      (libsource (lib "Miscellaneous Devices") (part "Cap Pol1"))
    )
    (comp (ref "C114")
      (value "NC")
      (footprint "0402_C")
      (description "贴片电容")
      (fields (field (name "PUBLISHER") "Altium Limited"))
      (libsource (lib "SX1276_e268v01a") (part "Cap"))
    )
    (comp (ref "C115")
      (value "10pF")
      (footprint "0402_C")
      (description "贴片电容")
      (fields (field (name "PUBLISHER") "Altium Limited"))
      (libsource (lib "SX1276_e268v01a") (part "Cap"))
    )
    (comp (ref "C116")
      (value "18pF")
      (footprint "0402_C")
      (description "贴片电容")
      (fields (field (name "PUBLISHER") "Altium Limited"))
      (libsource (lib "SX1276_e268v01a") (part "Cap"))
    )
    (comp (ref "C117")
      (value "NC")
      (footprint "0402_C")
      (description "贴片电容")
      (fields (field (name "PUBLISHER") "Altium Limited"))
      (libsource (lib "SX1276_e268v01a") (part "Cap"))
    )
    (comp (ref "C120")
      (value "10nF")
      (footprint "0402_C")
      (description "贴片电容")
      (libsource (lib "Emolib") (part "C_0603"))
    )
    (comp (ref "C121")
      (value "120pF")
      (footprint "0402_C")
      (description "贴片电容")
      (fields (field (name "PUBLISHER") "Altium Limited"))
      (libsource (lib "SX1276_e268v01a") (part "Cap"))
    )
    (comp (ref "C122")
      (value "NC")
      (footprint "0402_C")
      (description "贴片电容")
      (fields (field (name "PUBLISHER") "Altium Limited"))
      (libsource (lib "SX1276_e268v01a") (part "Cap"))
    )
    (comp (ref "C123")
      (value "22uF")
      (footprint "0805_C")
      (description "贴片电容")
      (fields (field (name "PUBLISHER") "Altium Limited"))
      (libsource (lib "Miscellaneous Devices") (part "Cap"))
    )
    (comp (ref "C124")
      (value "470uF 6.3V")
      (footprint "6.3x7.7")
      (description "电解电容器")
      (fields (field (name "PUBLISHER") "Altium Limited"))
      (libsource (lib "Miscellaneous Devices") (part "Cap Pol1"))
    )
    (comp (ref "C125")
      (value "120pF")
      (footprint "0402_C")
      (description "贴片电容")
      (fields (field (name "PUBLISHER") "Altium Limited"))
      (libsource (lib "SX1276_e268v01a") (part "Cap"))
    )
    (comp (ref "C126")
      (value "2.2nF")
      (footprint "0402_C")
      (description "贴片电容")
      (fields (field (name "PUBLISHER") "Altium Limited"))
      (libsource (lib "SX1276_e268v01a") (part "Cap"))
    )
    (comp (ref "C127")
      (value "120pF")
      (footprint "0603_C")
      (description "贴片电容")
      (libsource (lib "Emolib") (part "C_0603"))
    )
    (comp (ref "C128")
      (value "NC")
      (footprint "0402_C")
      (description "贴片电容")
      (fields (field (name "PUBLISHER") "Altium Limited"))
      (libsource (lib "SX1276_e268v01a") (part "Cap"))
    )
    (comp (ref "C129")
      (value "120pF")
      (footprint "0402_C")
      (description "贴片电容")
      (fields (field (name "PUBLISHER") "Altium Limited"))
      (libsource (lib "SX1276_e268v01a") (part "Cap"))
    )
    (comp (ref "C130")
      (value "NC")
      (footprint "0402_C")
      (description "贴片电容")
      (fields (field (name "PUBLISHER") "Altium Limited"))
      (libsource (lib "SX1276_e268v01a") (part "Cap"))
    )
    (comp (ref "C131")
      (value "NC")
      (footprint "0402_C")
      (description "贴片电容")
      (fields (field (name "PUBLISHER") "Altium Limited"))
      (libsource (lib "SX1276_e268v01a") (part "Cap"))
    )
    (comp (ref "C132")
      (value "120pF")
      (footprint "0402_C")
      (description "Capacitor SMD")
      (fields (field (name "PUBLISHER") "Altium Limited"))
      (libsource (lib "SX1276_e268v01a") (part "Cap"))
    )
    (comp (ref "C134")
      (value "120pF")
      (footprint "0603_C")
      (description "贴片电容")
      (libsource (lib "Emolib") (part "C_0603"))
    )
    (comp (ref "C135")
      (value "5pF")
      (footprint "0402_C")
      (description "贴片电容")
      (fields (field (name "PUBLISHER") "Altium Limited"))
      (libsource (lib "SX1276_e268v01a") (part "Cap"))
    )
    (comp (ref "C136")
      (value "NC")
      (footprint "0402_C")
      (description "贴片电容")
      (fields (field (name "PUBLISHER") "Altium Limited"))
      (libsource (lib "SX1276_e268v01a") (part "Cap"))
    )
    (comp (ref "C139")
      (value "120pF")
      (footprint "0402_C")
      (description "贴片电容")
      (fields (field (name "PUBLISHER") "Altium Limited"))
      (libsource (lib "SX1276_e268v01a") (part "Cap"))
    )
    (comp (ref "C140")
      (value "18pF")
      (footprint "0402_C")
      (description "贴片电容")
      (fields (field (name "PUBLISHER") "Altium Limited"))
      (libsource (lib "SX1276_e268v01a") (part "Cap"))
    )
    (comp (ref "D1")
      (value "SS34")
      (footprint "SMA")
      (description "Zener Diode")
      (fields (field (name "PUBLISHER") "Altium Limited"))
      (libsource (lib "Miscellaneous Devices") (part "D Zener"))
    )
    (comp (ref "D2")
      (value "HSC277")
      (footprint "SC-79")
      (description "二极管")
      (fields (field (name "PUBLISHER") "Altium Limited"))
      (libsource (lib "Miscellaneous Devices") (part "Diode 1N4149"))
    )
    (comp (ref "D3")
      (value "HSC277")
      (footprint "SC-79")
      (description "二极管")
      (fields (field (name "PUBLISHER") "Altium Limited"))
      (libsource (lib "Miscellaneous Devices") (part "Diode 1N4149"))
    )
    (comp (ref "D4")
      (value "HSC277")
      (footprint "SC-79")
      (description "二极管")
      (fields (field (name "PUBLISHER") "Altium Limited"))
      (libsource (lib "Miscellaneous Devices") (part "Diode 1N4149"))
    )
    (comp (ref "D5")
      (value "BZT52C4V3")
      (footprint "1206")
      (description "Zener Diode")
      (fields (field (name "PUBLISHER") "Altium Limited"))
      (libsource (lib "Miscellaneous Devices") (part "D Zener"))
    )
    (comp (ref "D6")
      (value "0402ESDA-09")
      (footprint "TSLP-2-20")
      (description "Zener Diode")
      (fields (field (name "PUBLISHER") "Altium Limited"))
      (libsource (lib "Miscellaneous Devices") (part "D Zener"))
    )
    (comp (ref "D7")
      (value "BA892")
      (footprint "LC-SOD-523:LC-SOD-523")
      (description "Silicon RF Switching Diode for VHF Band Switching in TV/VTR Tuners")
      (fields (field (name "PUBLISHER") "Altium Limited"))
      (libsource (lib "Infineon Discrete Diode") (part "BA592"))
    )
    (comp (ref "J4") (value "usb") (footprint "USB-MICRO") (libsource (lib "YT1_SCH_99SE") (part "usb")))
    (comp (ref "L1")
      (value "47nH")
      (footprint "0402_L")
      (description "贴片电感")
      (fields (field (name "PUBLISHER") "Altium Limited"))
      (libsource (lib "SX1276_e268v01a") (part "Inductor"))
    )
    (comp (ref "L2")
      (value "22uH")
      (footprint "SMNR4020-220M")
      (description "贴片电感")
      (fields (field (name "PUBLISHER") "Altium Limited"))
      (libsource (lib "SX1276_e268v01a") (part "Inductor"))
    )
    (comp (ref "L3")
      (value "4.7uH")
      (footprint "0603_L")
      (description "贴片电感")
      (fields (field (name "PUBLISHER") "Altium Limited"))
      (libsource (lib "Miscellaneous Devices") (part "Inductor"))
    )
    (comp (ref "L4")
      (value "47nH")
      (footprint "0402_L")
      (description "贴片电感")
      (fields (field (name "PUBLISHER") "Altium Limited"))
      (libsource (lib "SX1276_e268v01a") (part "Inductor"))
    )
    (comp (ref "L5")
      (value "47nH")
      (footprint "0402_L")
      (description "贴片电感")
      (fields (field (name "PUBLISHER") "Altium Limited"))
      (libsource (lib "SX1276_e268v01a") (part "Inductor"))
    )
    (comp (ref "L6")
      (value "47nH")
      (footprint "0402_L")
      (description "贴片电感")
      (fields (field (name "PUBLISHER") "Altium Limited"))
      (libsource (lib "SX1276_e268v01a") (part "Inductor"))
    )
    (comp (ref "L7")
      (value "15nH")
      (footprint "0402_L")
      (description "贴片电感")
      (fields (field (name "PUBLISHER") "Altium Limited"))
      (libsource (lib "SX1276_e268v01a") (part "Inductor"))
    )
    (comp (ref "L8")
      (value "7.5nH")
      (footprint "0402_L")
      (description "贴片电感")
      (fields (field (name "PUBLISHER") "Altium Limited"))
      (libsource (lib "SX1276_e268v01a") (part "Inductor"))
    )
    (comp (ref "L9")
      (value "12nH")
      (footprint "0603_L")
      (description "贴片电感")
      (fields (field (name "PUBLISHER") "Altium Limited"))
      (libsource (lib "SX1276_e268v01a") (part "Inductor"))
    )
    (comp (ref "L10")
      (value "15nH")
      (footprint "0402_L")
      (description "贴片电感")
      (fields (field (name "PUBLISHER") "Altium Limited"))
      (libsource (lib "SX1276_e268v01a") (part "Inductor"))
    )
    (comp (ref "L11")
      (value "18nH")
      (footprint "0402_L")
      (description "贴片电感")
      (fields (field (name "PUBLISHER") "Altium Limited"))
      (libsource (lib "SX1276_e268v01a") (part "Inductor"))
    )
    (comp (ref "L14")
      (value "0R")
      (footprint "0402_L")
      (description "贴片电阻")
      (fields (field (name "PUBLISHER") "Altium Limited"))
      (libsource (lib "SX1276_e268v01a") (part "Inductor"))
    )
    (comp (ref "L15")
      (value "47nH")
      (footprint "0402_L")
      (description "Inductor")
      (fields (field (name "PUBLISHER") "Altium Limited"))
      (libsource (lib "Miscellaneous Devices") (part "Inductor"))
    )
    (comp (ref "L16")
      (value "47nH")
      (footprint "0402_L")
      (description "Inductor")
      (fields (field (name "PUBLISHER") "Altium Limited"))
      (libsource (lib "Miscellaneous Devices") (part "Inductor"))
    )
    (comp (ref "L17")
      (value "NC")
      (footprint "0402_L")
      (description "Inductor")
      (fields (field (name "PUBLISHER") "Altium Limited"))
      (libsource (lib "Miscellaneous Devices") (part "Inductor"))
    )
    (comp (ref "L18")
      (value "12nH")
      (footprint "0805_L")
      (description "贴片电感")
      (fields (field (name "PUBLISHER") "Altium Limited"))
      (libsource (lib "SX1276_e268v01a") (part "Inductor"))
    )
    (comp (ref "L19")
      (value "33nH")
      (footprint "0908-12N")
      (description "贴片电感")
      (fields (field (name "Comment") "Inductor") (field (name "PUBLISHER") "Altium Limited"))
      (libsource (lib "SX1276_e268v01a") (part "Inductor"))
    )
    (comp (ref "L20")
      (value "47nH")
      (footprint "0402_L")
      (description "贴片电感")
      (fields (field (name "PUBLISHER") "Altium Limited"))
      (libsource (lib "SX1276_e268v01a") (part "Inductor"))
    )
    (comp (ref "L21")
      (value "47nH")
      (footprint "0402_L")
      (description "Inductor")
      (fields (field (name "PUBLISHER") "Altium Limited"))
      (libsource (lib "Miscellaneous Devices") (part "Inductor"))
    )
    (comp (ref "L23")
      (value "47nH")
      (footprint "0402_L")
      (description "Inductor")
      (fields (field (name "PUBLISHER") "Altium Limited"))
      (libsource (lib "Miscellaneous Devices") (part "Inductor"))
    )
    (comp (ref "L24")
      (value "0R")
      (footprint "0402_L")
      (description "贴片电阻")
      (fields (field (name "PUBLISHER") "Altium Limited"))
      (libsource (lib "SX1276_e268v01a") (part "Inductor"))
    )
    (comp (ref "L25")
      (value "18nH")
      (footprint "0402_L")
      (description "贴片电感")
      (fields (field (name "PUBLISHER") "Altium Limited"))
      (libsource (lib "SX1276_e268v01a") (part "Inductor"))
    )
    (comp (ref "L26")
      (value "12nH")
      (footprint "0402_L")
      (description "贴片电感")
      (fields (field (name "PUBLISHER") "Altium Limited"))
      (libsource (lib "SX1276_e268v01a") (part "Inductor"))
    )
    (comp (ref "L27")
      (value "18nH")
      (footprint "0402_L")
      (description "贴片电感")
      (fields (field (name "PUBLISHER") "Altium Limited"))
      (libsource (lib "SX1276_e268v01a") (part "Inductor"))
    )
    (comp (ref "L28")
      (value "18nH")
      (footprint "0402_L")
      (description "贴片电感")
      (fields (field (name "PUBLISHER") "Altium Limited"))
      (libsource (lib "SX1276_e268v01a") (part "Inductor"))
    )
    (comp (ref "LD1")
      (value "LED")
      (footprint "0603_LED_S1")
      (description "红灯")
      (libsource (lib "Emolib") (part "LED"))
    )
    (comp (ref "LD2")
      (value "LED")
      (footprint "0603_LED_S1")
      (description "绿灯")
      (libsource (lib "Emolib") (part "LED"))
    )
    (comp (ref "LS1")
      (value "Speaker")
      (footprint "PIN2")
      (description "Loudspeaker")
      (fields (field (name "PUBLISHER") "Altium Limited"))
      (libsource (lib "Miscellaneous Devices") (part "Speaker"))
    )
    (comp (ref "MK1")
      (value "Mic2")
      (footprint "4013_mic")
      (description "Microphone")
      (fields (field (name "PUBLISHER") "Altium Limited"))
      (libsource (lib "Miscellaneous Devices") (part "Mic2"))
    )
    (comp (ref "P2")
      (value "PJ30930-Q")
      (footprint "PJ30930-Q")
      (libsource (lib "Schlib2") (part "PJ30930-Q"))
    )
    (comp (ref "P3")
      (value "SMB")
      (footprint "SMB_V-RJ45")
      (description "SMB Straight Connector")
      (fields (field (name "PUBLISHER") "Altium Limited"))
      (libsource (lib "Miscellaneous Connectors") (part "SMB"))
    )
    (comp (ref "P4")
      (value "Header 2")
      (footprint "HDR1X2")
      (description "Header, 2-Pin")
      (fields (field (name "PUBLISHER") "Altium Limited"))
      (libsource (lib "Miscellaneous Connectors") (part "Header 2"))
    )
    (comp (ref "P5")
      (value "Header 8X2A")
      (footprint "HDR2X8_CEN")
      (description "Header, 8-Pin, Dual row")
      (fields (field (name "PUBLISHER") "Altium Limited"))
      (libsource (lib "Miscellaneous Connectors") (part "Header 8X2A"))
    )
    (comp (ref "P6")
      (value "Header 5")
      (footprint "HDR1X5")
      (description "Header, 5-Pin")
      (fields (field (name "PUBLISHER") "Altium Limited"))
      (libsource (lib "Miscellaneous Connectors") (part "Header 5"))
    )
    (comp (ref "P8")
      (value "Header 3")
      (footprint "电源插座")
      (description "Header, 3-Pin")
      (fields (field (name "PUBLISHER") "Altium Limited"))
      (libsource (lib "Miscellaneous Connectors") (part "Header 3"))
    )
    (comp (ref "P9")
      (value "Header 5")
      (footprint "HDR1X5")
      (description "Header, 5-Pin")
      (fields (field (name "PUBLISHER") "Altium Limited"))
      (libsource (lib "Miscellaneous Connectors") (part "Header 5"))
    )
    (comp (ref "P10")
      (value "Header 2")
      (footprint "HDR1X2")
      (description "Header, 2-Pin")
      (fields (field (name "PUBLISHER") "Altium Limited"))
      (libsource (lib "Miscellaneous Connectors") (part "Header 2"))
    )
    (comp (ref "Q1")
      (value "2SK3078A")
      (footprint "sot-89")
      (description "N-Channel MOSFET")
      (fields (field (name "PUBLISHER") "Altium Limited"))
      (libsource (lib "Miscellaneous Devices") (part "MOSFET-N"))
    )
    (comp (ref "Q2")
      (value "WST2339")
      (footprint "LC-SOT-23(SOT-23-3)")
      (description "P-Channel Power MOSFET")
      (fields (field (name "PUBLISHER") "Altium Limited"))
      (libsource (lib "Miscellaneous Devices") (part "PMOS-2"))
    )
    (comp (ref "Q3")
      (value "2SC3356")
      (footprint "LC-SOT-23(SOT-23-3)")
      (description "NPN Bipolar Transistor")
      (fields (field (name "PUBLISHER") "Altium Limited"))
      (libsource (lib "Miscellaneous Devices") (part "QNPN"))
    )
    (comp (ref "Q4")
      (value "BAT54C")
      (footprint "SOT-23-BAT54C")
      (libsource (lib "Newcapec9263") (part "BAT54C"))
    )
    (comp (ref "Q5")
      (value "NC")
      (footprint "LC-SC-75(SOT-523)")
      (description "NPN Resistor-equipped Transistor")
      (fields (field (name "PUBLISHER") "Altium Limited"))
      (libsource (lib "Philips Discrete BJT - Low Power") (part "PDTC114EEF"))
    )
    (comp (ref "Q6")
      (value "DTC114EE")
      (footprint "LC-SC-75(SOT-523)")
      (description "NPN Resistor-equipped Transistor")
      (fields (field (name "PUBLISHER") "Altium Limited"))
      (libsource (lib "Philips Discrete BJT - Low Power") (part "PDTC114EEF"))
    )
    (comp (ref "Q7")
      (value "BFP740ESD")
      (footprint "BFP740")
      (description "三极管")
      (libsource (lib "Schlib1") (part "NE3509"))
    )
    (comp (ref "Q8")
      (value "WST2339")
      (footprint "LC-SOT-23(SOT-23-3)")
      (description "P-Channel Power MOSFET")
      (fields (field (name "PUBLISHER") "Altium Limited"))
      (libsource (lib "Miscellaneous Devices") (part "PMOS-2"))
    )
    (comp (ref "Q9")
      (value "DTC114EE")
      (footprint "LC-SC-75(SOT-523)")
      (description "NPN Resistor-equipped Transistor")
      (fields (field (name "PUBLISHER") "Altium Limited"))
      (libsource (lib "Philips Discrete BJT - Low Power") (part "PDTC114EEF"))
    )
    (comp (ref "Q10")
      (value "RD02LUS2")
      (footprint "sot-89")
      (description "N-Channel MOSFET")
      (fields (field (name "PUBLISHER") "Altium Limited"))
      (libsource (lib "Miscellaneous Devices") (part "MOSFET-N"))
    )
    (comp (ref "R1")
      (value "1kR")
      (footprint "0402_R")
      (description "贴片电阻")
      (libsource (lib "Emolib") (part "R_0603"))
    )
    (comp (ref "R2")
      (value "1.5kR")
      (footprint "0402_R")
      (description "贴片电阻")
      (fields
        (field (name "MANUFACTURER") "Generic Components")
        (field (name "PUBLISHER") "Altium Hobart Technology Centre")
      )
      (libsource (lib "*") (part "Res2"))
    )
    (comp (ref "R3")
      (value "20kR")
      (footprint "0402_R")
      (description "贴片电阻")
      (libsource (lib "SX1276_e268v01a") (part "Resistor"))
    )
    (comp (ref "R4")
      (value "2.7kR")
      (footprint "0402_R")
      (description "贴片电阻")
      (libsource (lib "SX1276_e268v01a") (part "Resistor"))
    )
    (comp (ref "R5")
      (value "100kR")
      (footprint "0402_R")
      (description "贴片电阻")
      (fields (field (name "PUBLISHER") "Altium Limited"))
      (libsource (lib "Miscellaneous Devices") (part "Res2"))
    )
    (comp (ref "R6")
      (value "1kR")
      (footprint "0402_R")
      (description "贴片电阻")
      (libsource (lib "") (part "Resistor_1"))
    )
    (comp (ref "R7")
      (value "22R")
      (footprint "0402_R")
      (description "贴片电阻")
      (libsource (lib "SX1276_e268v01a") (part "Resistor"))
    )
    (comp (ref "R8")
      (value "130kR")
      (footprint "0402_R")
      (description "贴片电阻")
      (libsource (lib "SX1276_e268v01a") (part "Resistor"))
    )
    (comp (ref "R9")
      (value "10kR")
      (footprint "0402_R")
      (description "贴片电阻")
      (fields (field (name "PUBLISHER") "Altium Limited"))
      (libsource (lib "") (part "Res2_2"))
    )
    (comp (ref "R11")
      (value "680R")
      (footprint "0402_R")
      (description "贴片电阻")
      (libsource (lib "Emolib") (part "R_0603"))
    )
    (comp (ref "R12")
      (value "100kR")
      (footprint "0402_R")
      (description "贴片电阻")
      (libsource (lib "Emolib") (part "R_0603"))
    )
    (comp (ref "R13")
      (value "100kR")
      (footprint "0402_R")
      (description "贴片电阻")
      (fields (field (name "PUBLISHER") "Altium Limited"))
      (libsource (lib "Miscellaneous Devices") (part "Res2"))
    )
    (comp (ref "R14")
      (value "22R")
      (footprint "0402_R")
      (description "贴片电阻")
      (libsource (lib "") (part "RES_1"))
    )
    (comp (ref "R15")
      (value "22R")
      (footprint "0402_R")
      (description "贴片电阻")
      (libsource (lib "") (part "RES_1"))
    )
    (comp (ref "R16")
      (value "680R")
      (footprint "0402_R")
      (description "贴片电阻")
      (libsource (lib "") (part "RES_1"))
    )
    (comp (ref "R18")
      (value "10kR")
      (footprint "0402_R")
      (description "贴片电阻")
      (libsource (lib "") (part "RES_1"))
    )
    (comp (ref "R19")
      (value "100kR")
      (footprint "0402_R")
      (description "贴片电阻")
      (libsource (lib "我的元件") (part "RES"))
    )
    (comp (ref "R20")
      (value "100kR")
      (footprint "0402_R")
      (description "贴片电阻")
      (libsource (lib "") (part "RES_1"))
    )
    (comp (ref "R21")
      (value "1.5kR")
      (footprint "0402_R")
      (description "贴片电阻")
      (libsource (lib "我的元件") (part "RES"))
    )
    (comp (ref "R22")
      (value "100kR")
      (footprint "0402_R")
      (description "贴片电阻")
      (fields (field (name "PUBLISHER") "Altium Limited"))
      (libsource (lib "Miscellaneous Devices") (part "Res2"))
    )
    (comp (ref "R23")
      (value "100kR")
      (footprint "0402_R")
      (description "贴片电阻")
      (fields (field (name "PUBLISHER") "Altium Limited"))
      (libsource (lib "Miscellaneous Devices") (part "Res2"))
    )
    (comp (ref "R24")
      (value "NC")
      (footprint "0402_R")
      (description "贴片电阻")
      (libsource (lib "我的元件") (part "RES"))
    )
    (comp (ref "R25")
      (value "10kR")
      (footprint "0402_R")
      (description "贴片电阻")
      (fields (field (name "PUBLISHER") "Altium Limited"))
      (libsource (lib "") (part "Res2_2"))
    )
    (comp (ref "R26")
      (value "10kR")
      (footprint "0402_R")
      (description "贴片电阻")
      (fields (field (name "PUBLISHER") "Altium Limited"))
      (libsource (lib "") (part "Res2_2"))
    )
    (comp (ref "R27")
      (value "1kR")
      (footprint "0402_R")
      (description "贴片电阻")
      (libsource (lib "") (part "Resistor_1"))
    )
    (comp (ref "R28")
      (value "1kR")
      (footprint "0402_R")
      (description "贴片电阻")
      (libsource (lib "Emolib") (part "R_0603"))
    )
    (comp (ref "R29")
      (value "0R")
      (footprint "0402_R")
      (description "贴片电阻")
      (libsource (lib "") (part "Resistor_1"))
    )
    (comp (ref "R32")
      (value "4.3kΩ")
      (footprint "0402_R")
      (description "贴片电阻")
      (libsource (lib "") (part "Resistor_2"))
    )
    (comp (ref "R35")
      (value "5.6kR")
      (footprint "0402_R")
      (description "贴片电阻")
      (libsource (lib "") (part "Resistor_2"))
    )
    (comp (ref "R45")
      (value "10kR")
      (footprint "0402_R")
      (description "贴片电阻")
      (fields (field (name "PUBLISHER") "Altium Limited"))
      (libsource (lib "") (part "Res2_1"))
    )
    (comp (ref "R46")
      (value "NC")
      (footprint "0402_R")
      (description "贴片电阻")
      (libsource (lib "") (part "Resistor_1"))
    )
    (comp (ref "R47")
      (value "3kR")
      (footprint "0402_R")
      (description "贴片电阻")
      (libsource (lib "") (part "Resistor_3"))
    )
    (comp (ref "R48")
      (value "3.9kR")
      (footprint "0402_R")
      (description "贴片电阻")
      (libsource (lib "") (part "Resistor_2"))
    )
    (comp (ref "R49")
      (value "3.3kR")
      (footprint "0402_R")
      (description "贴片电阻")
      (libsource (lib "") (part "Resistor_1"))
    )
    (comp (ref "R50")
      (value "150R")
      (footprint "0402_R")
      (description "贴片电阻")
      (libsource (lib "我的元件") (part "RES"))
    )
    (comp (ref "R51")
      (value "56R")
      (footprint "0402_R")
      (description "贴片电阻")
      (libsource (lib "") (part "Resistor_1"))
    )
    (comp (ref "R52")
      (value "56R")
      (footprint "0402_R")
      (description "贴片电阻")
      (fields (field (name "PUBLISHER") "Altium Limited"))
      (libsource (lib "Miscellaneous Devices") (part "Res1"))
    )
    (comp (ref "S1")
      (value "SW-PB")
      (footprint "SW-SPST")
      (description "Switch")
      (fields (field (name "PUBLISHER") "Altium Limited"))
      (libsource (lib "Miscellaneous Devices") (part "SW-PB"))
    )
    (comp (ref "S2")
      (value "SW-PB")
      (footprint "SW-SPST")
      (description "Switch")
      (fields (field (name "PUBLISHER") "Altium Limited"))
      (libsource (lib "Miscellaneous Devices") (part "SW-PB"))
    )
    (comp (ref "U1")
      (value "RT9020")
      (footprint "LC-SOT-23-5")
      (libsource (lib "Schematic-2008-PGH") (part "RT9193"))
    )
    (comp (ref "U4")
      (value "SX1278")
      (footprint "SX1278")
      (description "SX1276 - Low Power Integrated UHF Transceiver with loRa Modem")
      (libsource (lib "SX1276_e268v01a") (part "SX1276"))
    )
    (comp (ref "U5")
      (value "PE4259")
      (footprint "SC70-6")
      (description "PE4259 Peregrine RF Switch")
      (libsource (lib "SX1276_e268v01a") (part "PE4259 RF Switch"))
    )
    (comp (ref "U6") (value "TP4054") (footprint "LC-SOT-23-5") (libsource (lib "MySchLib") (part "TP4054")))
    (comp (ref "U7")
      (value "PE4259")
      (footprint "SC70-6")
      (description "PE4259 Peregrine RF Switch")
      (libsource (lib "SX1276_e268v01a") (part "PE4259 RF Switch"))
    )
    (comp (ref "U8") (value "AT1846S") (footprint "AT1846S") (libsource (lib "Schlib1") (part "RDA846S")))
    (comp (ref "U9") (value "WM8974") (footprint "Wm8974") (libsource (lib "Schlib1") (part "WM8974")))
    (comp (ref "U10")
      (value "STM32F405RGT6")
      (footprint "TQFP64_L")
      (libsource (lib "STM32 F4") (part "STM32F405RGT6"))
    )
    (comp (ref "U12")
      (value "74AHC1G04")
      (footprint "LC-SOT-353")
      (description "反相器")
      (libsource (lib "Schlib2") (part "Component_1"))
    )
    (comp (ref "U13") (value "MT3608") (footprint "SOT23-6") (libsource (lib "Schlib2") (part "MT3608")))
    (comp (ref "U14") (value "W25Q64") (footprint "W25Q64") (libsource (lib "*") (part "W25Q64")))
    (comp (ref "Y1")
      (value "32Mhz")
      (footprint "nd3225da - nd2520da")
      (description "Crystal Oscillator")
      (fields (field (name "PUBLISHER") "Altium Limited"))
      (libsource (lib "Miscellaneous Devices") (part "XTAL"))
    )
    (comp (ref "Y2")
      (value "13MHz")
      (footprint "nd3225da - nd2520da")
      (description "Crystal Oscillator")
      (fields (field (name "PUBLISHER") "Altium Limited"))
      (libsource (lib "Miscellaneous Devices") (part "XTAL"))
    )
    (comp (ref "Y3")
      (value "8MHz")
      (footprint "nd3225da - nd2520da")
      (description "Crystal Oscillator")
      (fields (field (name "PUBLISHER") "Altium Limited"))
      (libsource (lib "Miscellaneous Devices") (part "XTAL"))
    )
    (comp (ref "Y4")
      (value "32.768KHz")
      (footprint "3215")
      (description "Crystal Oscillator")
      (fields (field (name "PUBLISHER") "Altium Limited"))
      (libsource (lib "Miscellaneous Devices") (part "XTAL"))
    )
  )
  (nets
    (net (code "1") (name "+3.3V") (class "Default")
      (node (ref "C100") (pin "1") (pinfunction "1_1") (pintype "passive"))
      (node (ref "C101") (pin "1") (pinfunction "1_1") (pintype "passive"))
      (node (ref "C102") (pin "1") (pinfunction "1_1") (pintype "passive"))
      (node (ref "C14") (pin "1") (pinfunction "1_1") (pintype "passive"))
      (node (ref "C20") (pin "2") (pinfunction "2_2") (pintype "passive"))
      (node (ref "C26") (pin "2") (pinfunction "2_2") (pintype "passive"))
      (node (ref "C27") (pin "2") (pinfunction "2_2") (pintype "passive"))
      (node (ref "C31") (pin "1") (pinfunction "1_1") (pintype "passive"))
      (node (ref "C33") (pin "2") (pinfunction "2_2") (pintype "passive"))
      (node (ref "C4") (pin "1") (pinfunction "1_1") (pintype "passive"))
      (node (ref "C41") (pin "2") (pintype "passive"))
      (node (ref "C42") (pin "2") (pintype "passive"))
      (node (ref "C43") (pin "2") (pintype "passive"))
      (node (ref "C44") (pin "1") (pintype "passive"))
      (node (ref "C45") (pin "2") (pintype "passive"))
      (node (ref "C46") (pin "2") (pintype "passive"))
      (node (ref "C47") (pin "1") (pintype "passive"))
      (node (ref "C48") (pin "2") (pintype "passive"))
      (node (ref "C5") (pin "1") (pinfunction "1_1") (pintype "passive"))
      (node (ref "C53") (pin "1") (pintype "passive"))
      (node (ref "C55") (pin "1") (pintype "passive"))
      (node (ref "C57") (pin "1") (pintype "passive"))
      (node (ref "C58") (pin "1") (pintype "passive"))
      (node (ref "C59") (pin "1") (pintype "passive"))
      (node (ref "C60") (pin "2") (pintype "passive"))
      (node (ref "C63") (pin "2") (pintype "passive"))
      (node (ref "C69") (pin "1") (pinfunction "1_1") (pintype "passive"))
      (node (ref "C7") (pin "1") (pintype "passive"))
      (node (ref "C70") (pin "1") (pinfunction "1_1") (pintype "passive"))
      (node (ref "C71") (pin "1") (pinfunction "1_1") (pintype "passive"))
      (node (ref "C97") (pin "2") (pintype "passive"))
      (node (ref "D5") (pin "2") (pinfunction "K_2") (pintype "passive"))
      (node (ref "L3") (pin "1") (pinfunction "1_1") (pintype "passive"))
      (node (ref "P4") (pin "1") (pinfunction "1_1") (pintype "passive"))
      (node (ref "P5") (pin "11") (pinfunction "11_11") (pintype "passive"))
      (node (ref "P5") (pin "12") (pinfunction "12_12") (pintype "passive"))
      (node (ref "P6") (pin "2") (pinfunction "2_2") (pintype "passive"))
      (node (ref "Q2") (pin "3") (pinfunction "S_3") (pintype "passive"))
      (node (ref "Q4") (pin "1") (pinfunction "1_1") (pintype "passive"))
      (node (ref "Q8") (pin "3") (pinfunction "S_3") (pintype "passive"))
      (node (ref "R1") (pin "2") (pintype "passive"))
      (node (ref "R13") (pin "2") (pinfunction "2_2") (pintype "passive"))
      (node (ref "R25") (pin "2") (pinfunction "2_2") (pintype "passive"))
      (node (ref "R26") (pin "2") (pinfunction "2_2") (pintype "passive"))
      (node (ref "R28") (pin "2") (pintype "passive"))
      (node (ref "R29") (pin "2") (pinfunction "2_2") (pintype "passive"))
      (node (ref "R45") (pin "2") (pinfunction "2_2") (pintype "passive"))
      (node (ref "R5") (pin "2") (pinfunction "2_2") (pintype "passive"))
      (node (ref "R7") (pin "2") (pinfunction "2_2") (pintype "passive"))
      (node (ref "U1") (pin "5") (pinfunction "VOUT_5") (pintype "passive"))
      (node (ref "U10") (pin "19") (pinfunction "VDD_19") (pintype "power_in"))
      (node (ref "U10") (pin "32") (pinfunction "VDD_32") (pintype "power_in"))
      (node (ref "U10") (pin "48") (pinfunction "VDD_48") (pintype "power_in"))
      (node (ref "U10") (pin "64") (pinfunction "VDD_64") (pintype "power_in"))
      (node (ref "U12") (pin "5") (pinfunction "VCC_5") (pintype "passive"))
      (node (ref "U14") (pin "3") (pinfunction "/WP(IO2)_3") (pintype "passive"))
      (node (ref "U14") (pin "7") (pinfunction "/HOLD(IO3)_7") (pintype "passive"))
      (node (ref "U14") (pin "8") (pinfunction "VCC_8") (pintype "passive"))
      (node (ref "U4") (pin "14") (pinfunction "VBAT3_14") (pintype "passive"))
      (node (ref "U4") (pin "24") (pinfunction "VBAT2_24") (pintype "passive"))
      (node (ref "U4") (pin "3") (pinfunction "VBAT1_3") (pintype "passive"))
      (node (ref "U5") (pin "6") (pinfunction "VDD_6") (pintype "passive"))
      (node (ref "U7") (pin "6") (pinfunction "VDD_6") (pintype "passive"))
      (node (ref "U8") (pin "1") (pinfunction "AVDD_1") (pintype "passive"))
      (node (ref "U8") (pin "13") (pinfunction "AVDD_13") (pintype "passive"))
      (node (ref "U8") (pin "16") (pinfunction "AVDD_16") (pintype "passive"))
      (node (ref "U8") (pin "21") (pinfunction "AVDD_21") (pintype "passive"))
      (node (ref "U8") (pin "23") (pinfunction "AVDD_23") (pintype "passive"))
      (node (ref "U8") (pin "4") (pinfunction "AVDD_4") (pintype "passive"))
      (node (ref "U9") (pin "2") (pinfunction "AVDD_2") (pintype "passive"))
      (node (ref "U9") (pin "4") (pinfunction "DCVDD_4") (pintype "passive"))
      (node (ref "U9") (pin "5") (pinfunction "DBVDD_5") (pintype "passive"))
    )
    (net (code "2") (name "+5V") (class "Default")
      (node (ref "C2") (pin "2") (pinfunction "2_2") (pintype "passive"))
      (node (ref "C79") (pin "2") (pintype "passive"))
      (node (ref "D1") (pin "2") (pinfunction "K_2") (pintype "passive"))
      (node (ref "P5") (pin "1") (pinfunction "1_1") (pintype "passive"))
      (node (ref "P5") (pin "2") (pinfunction "2_2") (pintype "passive"))
      (node (ref "R3") (pin "2") (pinfunction "2_2") (pintype "passive"))
      (node (ref "U9") (pin "20") (pinfunction "SPKVDD_20") (pintype "passive"))
    )
    (net (code "3") (name "/5V_EN") (class "Default")
      (node (ref "R29") (pin "1") (pinfunction "1_1") (pintype "passive"))
      (node (ref "R46") (pin "1") (pinfunction "1_1") (pintype "passive"))
      (node (ref "U13") (pin "4") (pinfunction "EN_4") (pintype "passive"))
    )
    (net (code "4") (name "/1278_DIO0") (class "Default")
      (node (ref "U10") (pin "30") (pinfunction "PB11/I2C2_SDA/USART3_RX/OTG_HS_ULPI_D4/ETH_RMII_TX_EN/ETH_MII_TX_EN/TIM2_CH4/EVENTOUT_30") (pintype "bidirectional"))
      (node (ref "U4") (pin "8") (pinfunction "DIO0_8") (pintype "passive"))
    )
    (net (code "5") (name "/1278_DIO1") (class "Default")
      (node (ref "U10") (pin "37") (pinfunction "PC6/I2S2_MCK/TIM8_CH1/SDIO_D6/USART6_TX/DCMI_D0/TIM3_CH1/EVENTOUT_37") (pintype "bidirectional"))
      (node (ref "U4") (pin "9") (pinfunction "DIO1_9") (pintype "passive"))
    )
    (net (code "6") (name "/1278_DIO2") (class "Default")
      (node (ref "U10") (pin "27") (pinfunction "PB1/TIM3_CH4/TIM8_CH3N/OTG_HS_ULPI_D2/ETH_MII_RXD3/OTG_HS_INTN/TIM1_CH3N/EVENTOUT/ADC12_IN9_27") (pintype "bidirectional"))
      (node (ref "U4") (pin "10") (pinfunction "DIO2_10") (pintype "passive"))
    )
    (net (code "7") (name "/1278_DIO3") (class "Default")
      (node (ref "U10") (pin "29") (pinfunction "PB10/SPI2_SCK/I2S2_CK/I2C2_SCL/USART3_TX/OTG_HS_ULPI_D3/ETH_MII_RX_ER/TIM2_CH3/EVENTOUT_29") (pintype "bidirectional"))
      (node (ref "U4") (pin "11") (pinfunction "DIO3_11") (pintype "passive"))
    )
    (net (code "8") (name "/1278_DIO4") (class "Default")
      (node (ref "U10") (pin "39") (pinfunction "PC8/TIM8_CH3/SDIO_D0/TIM3_CH3/USART6_CK/DCMI_D2/EVENTOUT_39") (pintype "bidirectional"))
      (node (ref "U4") (pin "12") (pinfunction "DIO4_12") (pintype "passive"))
    )
    (net (code "9") (name "/1278_DIO5") (class "Default")
      (node (ref "U10") (pin "42") (pinfunction "PA9/USART1_TX/TIM1_CH2/I2C3_SMBA/DCMI_D0/EVENTOUT/OTG_FS_VBUS_42") (pintype "bidirectional"))
      (node (ref "U4") (pin "13") (pinfunction "DIO5_13") (pintype "passive"))
    )
    (net (code "10") (name "/1278_MISO") (class "Default")
      (node (ref "U10") (pin "22") (pinfunction "PA6/SPI1_MISO/TIM8_BKIN/TIM13_CH1/DCMI_PIXCLK/TIM3_CH1/TIM1_BKIN/EVENTOUT/ADC12_IN6_22") (pintype "bidirectional"))
      (node (ref "U4") (pin "17") (pinfunction "MISO_17") (pintype "passive"))
    )
    (net (code "11") (name "/1278_MOSI") (class "Default")
      (node (ref "U10") (pin "23") (pinfunction "PA7/SPI1_MOSI/TIM8_CH1N/TIM14_CH1/TIM3_CH2/ETH_MII_RX_DV/TIM1_CH1N/RMII_CRS_DV/EVENTOUT/ADC12_IN7_23") (pintype "bidirectional"))
      (node (ref "U4") (pin "18") (pinfunction "MOSI_18") (pintype "passive"))
    )
    (net (code "12") (name "/1278_NSS") (class "Default")
      (node (ref "U10") (pin "20") (pinfunction "PA4/SPI1_NSS/SPI3_NSS/USART2_CK/DCMI_HSYNC/OTG_HS_SOF/I2S3_WS/EVENTOUT/ADC12_IN4/DAC1_OUT_20") (pintype "bidirectional"))
      (node (ref "U4") (pin "19") (pinfunction "NSS_19") (pintype "passive"))
    )
    (net (code "13") (name "/1278_SCK") (class "Default")
      (node (ref "U10") (pin "21") (pinfunction "PA5/SPI1_SCK/OTG_HS_ULPI_CK/TIM2_CH1_ETR/TIM8_CHIN/EVENTOUT/ADC12_IN5/DAC2_OUT_21") (pintype "bidirectional"))
      (node (ref "U4") (pin "16") (pinfunction "SCK_16") (pintype "passive"))
    )
    (net (code "14") (name "/1846_AFOUT") (class "Default")
      (node (ref "C52") (pin "2") (pintype "passive"))
      (node (ref "U8") (pin "9") (pinfunction "AFOUT_9") (pintype "passive"))
    )
    (net (code "15") (name "/1846_CODE_IN{slash}CODE_OUT") (class "Default")
      (node (ref "U10") (pin "59") (pinfunction "PB7/I2C1_SDA/FSMC_NL/DCMI_VSYNC/USART1_RX/TIM4_CH2/EVENTOUT_59") (pintype "bidirectional"))
      (node (ref "U8") (pin "31") (pinfunction "GPIO1/CODE_IN/CODE_OUT_31") (pintype "passive"))
    )
    (net (code "16") (name "/1846_CSS_IN{slash}CSS_OUT") (class "Default")
      (node (ref "U10") (pin "62") (pinfunction "PB9/SPI2_NSS/I2S2_WS/TIM4_CH4/TIM11_CH1/SDIO_D5/DCMI_D7/I2C1_SDA/CAN1_TX/EVENTOUT_62") (pintype "bidirectional"))
      (node (ref "U8") (pin "32") (pinfunction "GPIO0/CSS_IN/CSS_OUT_32") (pintype "passive"))
    )
    (net (code "17") (name "/1846_GPIO2{slash}INT") (class "Default")
      (node (ref "U10") (pin "58") (pinfunction "PB6/I2C1_SCL/TIM4_CH1/CAN2_TX/DCMI_D5/USART1_TX/EVENTOUT_58") (pintype "bidirectional"))
      (node (ref "U8") (pin "30") (pinfunction "GPIO2/INT_30") (pintype "passive"))
    )
    (net (code "18") (name "/1846_GPIO3{slash}SDO") (class "Default")
      (node (ref "U10") (pin "2") (pinfunction "PC13/EVENTOUT/RTC_AF1_2") (pintype "bidirectional"))
      (node (ref "U8") (pin "29") (pinfunction "GPIO3/SDO_29") (pintype "passive"))
    )
    (net (code "19") (name "/1846_GPIO4{slash}RXON") (class "Default")
      (node (ref "LD2") (pin "2") (pinfunction "K_2") (pintype "passive"))
      (node (ref "U10") (pin "26") (pinfunction "PB0/TIM3_CH3/TIM8_CH2N/OTG_HS_ULPI_D1/ETH_MII_RXD2/TIM1_CH2N/EVENTOUT/ADC12_IN8_26") (pintype "bidirectional"))
      (node (ref "U8") (pin "28") (pinfunction "GPIO4/RXON_28") (pintype "passive"))
    )
    (net (code "20") (name "/1846_GPIO5{slash}TXON") (class "Default")
      (node (ref "U10") (pin "57") (pinfunction "PB5/I2C1_SMBA/CAN2_RX/OTG_HS_ULPI_D7/ETH_PPS_OUT/TIM3_CH2/SPI1_MOSI/SPI3_MOSI/DCMI_D10/I2S3_SD/EVENTOUT_57") (pintype "bidirectional"))
      (node (ref "U8") (pin "27") (pinfunction "GPIO5/TXON_27") (pintype "passive"))
    )
    (net (code "21") (name "/1846_GPIO6{slash}SQ") (class "Default")
      (node (ref "U10") (pin "10") (pinfunction "PC2/SPI2_MISO/OTG_HS_ULPI_DIR/TH_MII_TXD2/I2S2ext_SD/EVENTOUT/ADC123_IN12_10") (pintype "bidirectional"))
      (node (ref "U8") (pin "26") (pinfunction "GPIO6/SQ_26") (pintype "passive"))
    )
    (net (code "22") (name "/1846_GPIO7{slash}VOX") (class "Default")
      (node (ref "U10") (pin "11") (pinfunction "PC3/SPI2_MOSI/I2S2_SD/OTG_HS_ULPI_NXT/ETH_MII_TX_CLK/EVENTOUT/ADC123_IN13_11") (pintype "bidirectional"))
      (node (ref "U8") (pin "25") (pinfunction "GPIO7/VOX_25") (pintype "passive"))
    )
    (net (code "23") (name "/1846_PDN") (class "Default")
      (node (ref "C94") (pin "1") (pinfunction "1_1") (pintype "passive"))
      (node (ref "U12") (pin "4") (pinfunction "Y_4") (pintype "passive"))
      (node (ref "U8") (pin "24") (pinfunction "PDN_24") (pintype "passive"))
    )
    (net (code "24") (name "/8974_ADC") (class "Default")
      (node (ref "U10") (pin "52") (pinfunction "PC11/UART4_RX/SPI3_MISO/SDIO_D3/DCMI_D4/USART3_RX/I2S3ext_SD/EVENTOUT_52") (pintype "bidirectional"))
      (node (ref "U9") (pin "7") (pinfunction "ADCDAT_7") (pintype "passive"))
    )
    (net (code "25") (name "/8974_BCLK") (class "Default")
      (node (ref "U10") (pin "51") (pinfunction "PC10/SPI3_SCK/I2S3_CK/UART4_TX/SDIO_D2/DCMI_D8/USART3_TX/EVENTOUT_51") (pintype "bidirectional"))
      (node (ref "U9") (pin "10") (pinfunction "BCLK_10") (pintype "passive"))
    )
    (net (code "26") (name "/8974_DAC") (class "Default")
      (node (ref "U10") (pin "53") (pinfunction "PC12/UART5_TX/SDIO_CK/DCMI_D9/SPI3_MOSI/I2S3_SD/USART3_CK/EVENTOUT_53") (pintype "bidirectional"))
      (node (ref "U9") (pin "8") (pinfunction "DACDAT_8") (pintype "passive"))
    )
    (net (code "27") (name "/8974_FRAME") (class "Default")
      (node (ref "U10") (pin "50") (pinfunction "PA15(JTDI)/JTDI/SPI3_NSS/I2S3_WS/TIM2_CH1_ETR/SPI1_NSS/EVENTOUT_50") (pintype "bidirectional"))
      (node (ref "U9") (pin "9") (pinfunction "FRAME_9") (pintype "passive"))
    )
    (net (code "28") (name "/8974_MCLK") (class "Default")
      (node (ref "U10") (pin "38") (pinfunction "PC7/I2S3_MCK/TIM8_CH2/SDIO_D7/USART6_RX/DCMI_D1/TIM3_CH2/EVENTOUT_38") (pintype "bidirectional"))
      (node (ref "U9") (pin "11") (pinfunction "MCLK_11") (pintype "passive"))
    )
    (net (code "29") (name "/ADC") (class "Default")
      (node (ref "C99") (pin "2") (pinfunction "2_2") (pintype "passive"))
      (node (ref "P9") (pin "5") (pinfunction "5_5") (pintype "passive"))
      (node (ref "R45") (pin "1") (pinfunction "1_1") (pintype "passive"))
      (node (ref "R9") (pin "2") (pinfunction "2_2") (pintype "passive"))
      (node (ref "S2") (pin "1") (pinfunction "1_1") (pintype "passive"))
      (node (ref "U10") (pin "8") (pinfunction "PC0/OTG_HS_ULPI_STP/EVENTOUT/ADC123_IN10_8") (pintype "bidirectional"))
    )
    (net (code "30") (name "/BAT_Dect") (class "Default")
      (node (ref "C84") (pin "1") (pintype "passive"))
      (node (ref "R22") (pin "1") (pinfunction "1_1") (pintype "passive"))
      (node (ref "R23") (pin "2") (pinfunction "2_2") (pintype "passive"))
      (node (ref "R46") (pin "2") (pinfunction "2_2") (pintype "passive"))
      (node (ref "U10") (pin "9") (pinfunction "PC1/ETH_MDC/EVENTOUT/ADC123_IN11_9") (pintype "bidirectional"))
    )
    (net (code "31") (name "/BOOT0") (class "Default")
      (node (ref "R18") (pin "2") (pinfunction "2_2") (pintype "passive"))
      (node (ref "R19") (pin "2") (pinfunction "2_2") (pintype "passive"))
      (node (ref "U10") (pin "60") (pinfunction "BOOT0/VPP_60") (pintype "input"))
    )
    (net (code "32") (name "/BOOT1") (class "Default")
      (node (ref "R20") (pin "2") (pinfunction "2_2") (pintype "passive"))
      (node (ref "U10") (pin "28") (pinfunction "PB2-BOOT1(PB2)/EVENTOUT_28") (pintype "bidirectional"))
    )
    (net (code "33") (name "/CLK") (class "Default")
      (node (ref "P6") (pin "5") (pinfunction "5_5") (pintype "passive"))
      (node (ref "P9") (pin "4") (pinfunction "4_4") (pintype "passive"))
      (node (ref "U10") (pin "49") (pinfunction "PA14(JTCK-SWCLK)/JTCK-SWCLK/EVENTOUT_49") (pintype "bidirectional"))
    )
    (net (code "34") (name "/DIO") (class "Default")
      (node (ref "P6") (pin "4") (pinfunction "4_4") (pintype "passive"))
      (node (ref "P9") (pin "3") (pinfunction "3_3") (pintype "passive"))
      (node (ref "U10") (pin "46") (pinfunction "PA13(JTMS-SWDIO)/JTMS-SWDIO/EVENTOUT_46") (pintype "bidirectional"))
    )
    (net (code "35") (name "/EarphoneL") (class "Default")
      (node (ref "LS1") (pin "2") (pinfunction "2_2") (pintype "passive"))
      (node (ref "P2") (pin "5") (pintype "passive"))
    )
    (net (code "36") (name "/EarphoneR") (class "Default")
      (node (ref "LS1") (pin "1") (pinfunction "1_1") (pintype "passive"))
      (node (ref "P2") (pin "6") (pintype "passive"))
    )
    (net (code "37") (name "/I2C3_SCL") (class "Default")
      (node (ref "P9") (pin "1") (pinfunction "1_1") (pintype "passive"))
      (node (ref "R25") (pin "1") (pinfunction "1_1") (pintype "passive"))
      (node (ref "U10") (pin "41") (pinfunction "PA8/MCO1/USART1_CK/TIM1_CH1/I2C3_SCL/OTG_FS_SOF/EVENTOUT_41") (pintype "bidirectional"))
      (node (ref "U8") (pin "2") (pinfunction "SCLK_2") (pintype "passive"))
      (node (ref "U9") (pin "13") (pinfunction "SCLK_13") (pintype "passive"))
    )
    (net (code "38") (name "/I2C3_SDA") (class "Default")
      (node (ref "P9") (pin "2") (pinfunction "2_2") (pintype "passive"))
      (node (ref "R26") (pin "1") (pinfunction "1_1") (pintype "passive"))
      (node (ref "U10") (pin "40") (pinfunction "PC9/I2S_CKIN/MCO2/TIM8_CH4/SDIO_D1//I2C3_SDA/DCMI_D3/TIM3_CH4/EVENTOUT_40") (pintype "bidirectional"))
      (node (ref "U8") (pin "3") (pinfunction "SDIO_3") (pintype "passive"))
      (node (ref "U9") (pin "14") (pinfunction "SDIN_14") (pintype "passive"))
    )
    (net (code "39") (name "/MIC") (class "Default")
      (node (ref "MK1") (pin "1") (pinfunction "1_1") (pintype "passive"))
      (node (ref "P2") (pin "8") (pintype "passive"))
    )
    (net (code "40") (name "/MICN") (class "Default")
      (node (ref "C56") (pin "1") (pintype "passive"))
      (node (ref "C61") (pin "1") (pintype "passive"))
      (node (ref "P2") (pin "1") (pintype "passive"))
      (node (ref "R11") (pin "1") (pintype "passive"))
      (node (ref "R12") (pin "2") (pintype "passive"))
      (node (ref "R9") (pin "1") (pinfunction "1_1") (pintype "passive"))
    )
    (net (code "41") (name "/MONOOUT") (class "Default")
      (node (ref "C40") (pin "1") (pintype "passive"))
      (node (ref "U8") (pin "11") (pinfunction "MIC_IN_11") (pintype "passive"))
    )
    (net (code "42") (name "/NRST") (class "Default")
      (node (ref "C64") (pin "2") (pinfunction "2_2") (pintype "passive"))
      (node (ref "R13") (pin "1") (pinfunction "1_1") (pintype "passive"))
      (node (ref "S1") (pin "2") (pinfunction "2_2") (pintype "passive"))
      (node (ref "U10") (pin "7") (pinfunction "NRST_7") (pintype "bidirectional"))
    )
    (net (code "43") (name "/OSC32_IN") (class "Default")
      (node (ref "C67") (pin "2") (pinfunction "2_2") (pintype "passive"))
      (node (ref "U10") (pin "3") (pinfunction "PC14-OSC32_IN(PC14)/EVENTOUT/OSC32_IN_3") (pintype "bidirectional"))
      (node (ref "Y4") (pin "1") (pinfunction "OSC1_1") (pintype "passive"))
    )
    (net (code "44") (name "/OSC32_OUT") (class "Default")
      (node (ref "C68") (pin "2") (pinfunction "2_2") (pintype "passive"))
      (node (ref "U10") (pin "4") (pinfunction "PC15-OSC32_OUT(PC15)/EVENTOUT/OSC32_OUT_4") (pintype "bidirectional"))
      (node (ref "Y4") (pin "2") (pinfunction "OSC2_2") (pintype "passive"))
    )
    (net (code "45") (name "/OSC_IN") (class "Default")
      (node (ref "C65") (pin "2") (pinfunction "2_2") (pintype "passive"))
      (node (ref "U10") (pin "5") (pinfunction "PH0-OSC_IN(PH0)/EVENTOUT/OSC_IN_5") (pintype "bidirectional"))
      (node (ref "Y3") (pin "2") (pinfunction "OSC2_2") (pintype "passive"))
    )
    (net (code "46") (name "/OSC_OUT") (class "Default")
      (node (ref "C66") (pin "2") (pinfunction "2_2") (pintype "passive"))
      (node (ref "U10") (pin "6") (pinfunction "PH1-OSC_OUT(PH1)/EVENTOUT/OSC_OUT_6") (pintype "bidirectional"))
      (node (ref "Y3") (pin "1") (pinfunction "OSC1_1") (pintype "passive"))
    )
    (net (code "47") (name "/PA10-ID") (class "Default")
      (node (ref "R16") (pin "1") (pinfunction "1_1") (pintype "passive"))
      (node (ref "U10") (pin "43") (pinfunction "PA10/USART1_RX/TIM1_CH3/OTG_FS_ID/DCMI_D1/EVENTOUT_43") (pintype "bidirectional"))
    )
    (net (code "48") (name "/PA11{slash}USB_DM") (class "Default")
      (node (ref "R14") (pin "1") (pinfunction "1_1") (pintype "passive"))
      (node (ref "U10") (pin "44") (pinfunction "PA11/USART1_CTS/CAN1_RX/TIM1_CH4/OTG_FS_DM/EVENTOUT_44") (pintype "bidirectional"))
    )
    (net (code "49") (name "/PA12{slash}USB_DP") (class "Default")
      (node (ref "R15") (pin "1") (pinfunction "1_1") (pintype "passive"))
      (node (ref "U10") (pin "45") (pinfunction "PA12/USART1_RTS/CAN1_TX/TIM1_ETR/OTG_FS_DP/EVENTOUT_45") (pintype "bidirectional"))
    )
    (net (code "50") (name "/RF_switch") (class "Default")
      (node (ref "C28") (pin "2") (pinfunction "2_2") (pintype "passive"))
      (node (ref "C39") (pin "2") (pinfunction "2_2") (pintype "passive"))
      (node (ref "U10") (pin "24") (pinfunction "PC4/ETH_RMII_RX_D0/ETH_MII_RX_D0/EVENTOUT/ADC12_IN14_24") (pintype "bidirectional"))
      (node (ref "U12") (pin "2") (pinfunction "A_2") (pintype "passive"))
      (node (ref "U5") (pin "4") (pinfunction "CTRL_4") (pintype "passive"))
      (node (ref "U7") (pin "4") (pinfunction "CTRL_4") (pintype "passive"))
    )
    (net (code "51") (name "/SPKOUTN") (class "Default")
      (node (ref "C113") (pin "2") (pinfunction "2_2") (pintype "passive"))
      (node (ref "P2") (pin "3") (pintype "passive"))
    )
    (net (code "52") (name "/SPKOUTP") (class "Default")
      (node (ref "C83") (pin "2") (pinfunction "2_2") (pintype "passive"))
      (node (ref "P2") (pin "2") (pintype "passive"))
    )
    (net (code "53") (name "/TP4054_~{CHRG}") (class "Default")
      (node (ref "U10") (pin "61") (pinfunction "PB8/TIM4_CH3/SDIO_D4/TIM10_CH1/DCMI_D6/ETH_MII_TXD3/I2C1_SCL/CAN1_RX/EVENTOUT_61") (pintype "bidirectional"))
      (node (ref "U6") (pin "1") (pinfunction "~{CHRG}_1") (pintype "passive"))
    )
    (net (code "54") (name "/USART2_RX") (class "Default")
      (node (ref "P5") (pin "6") (pinfunction "6_6") (pintype "passive"))
      (node (ref "U10") (pin "17") (pinfunction "PA3/USART2_RX/TIM5_CH4/TIM9_CH2/TIM2_CH4/OTG_HS_ULPI_D0/ETH_MII_COL/EVENTOUT/ADC123_IN3_17") (pintype "bidirectional"))
    )
    (net (code "55") (name "/USART2_TX") (class "Default")
      (node (ref "P5") (pin "5") (pinfunction "5_5") (pintype "passive"))
      (node (ref "U10") (pin "16") (pinfunction "PA2/USART2_TX/TIM5_CH3/TIM9_CH1/TIM2_CH3/ETH_MDIO/EVENTOUT/ADC123_IN2_16") (pintype "bidirectional"))
    )
    (net (code "56") (name "/USART4_RX") (class "Default")
      (node (ref "P5") (pin "8") (pinfunction "8_8") (pintype "passive"))
      (node (ref "U10") (pin "15") (pinfunction "PA1/USART2_RTS/UART4_RX/ETH_RMII_REF_CLK/ETH_MII_RX_CLK/TIM5_CH2/TIM2_CH2/EVENTOUT/ADC123_IN1_15") (pintype "bidirectional"))
    )
    (net (code "57") (name "/USART4_TX") (class "Default")
      (node (ref "P5") (pin "7") (pinfunction "7_7") (pintype "passive"))
      (node (ref "U10") (pin "14") (pinfunction "PA0-WKUP(PA0)/USART2_CTS/UART4_TX/ETH_MII_CRS/TIM2_CH1_ETR/TIM5_CH1/TIM8_ETR/EVENTOUT/ADC123_IN0/WKUP_14") (pintype "bidirectional"))
    )
    (net (code "58") (name "/VBAT2") (class "Default")
      (node (ref "C98") (pin "1") (pintype "passive"))
      (node (ref "Q4") (pin "3") (pinfunction "3_3") (pintype "passive"))
      (node (ref "U10") (pin "1") (pinfunction "VBAT_1") (pintype "power_in"))
    )
    (net (code "59") (name "/W25Q64_MISO") (class "Default")
      (node (ref "P5") (pin "14") (pinfunction "14_14") (pintype "passive"))
      (node (ref "U10") (pin "35") (pinfunction "PB14/SPI2_MISO/TIM1_CH2N/TIM12_CH1/OTG_HS_DM/USART3_RTS/TIM8_CH2N/I2S2ext_SD/EVENTOUT_35") (pintype "bidirectional"))
      (node (ref "U14") (pin "2") (pinfunction "DO(IO1)_2") (pintype "passive"))
    )
    (net (code "60") (name "/W25Q64_MOSI") (class "Default")
      (node (ref "P5") (pin "16") (pinfunction "16_16") (pintype "passive"))
      (node (ref "U10") (pin "36") (pinfunction "PB15/SPI2_MOSI/I2S2_SD/TIM1_CH3N/TIM8_CH3N/TIM12_CH2/OTG_HS_DP/EVENTOUT_36") (pintype "bidirectional"))
      (node (ref "U14") (pin "5") (pinfunction "DI(IO0)_5") (pintype "passive"))
    )
    (net (code "61") (name "/W25Q64_NSS") (class "Default")
      (node (ref "P5") (pin "13") (pinfunction "13_13") (pintype "passive"))
      (node (ref "U10") (pin "33") (pinfunction "PB12/SPI2_NSS/I2S2_WS/I2C2_SMBA/USART3_CK/TIM1_BKIN/CAN2_RX/OTG_HS_ULPI_D5/ETH_RMII_TXD0/ETH_MII_TXD0/OTG_HS_ID/EVENTOUT_33") (pintype "bidirectional"))
      (node (ref "U14") (pin "1") (pinfunction "/CS_1") (pintype "passive"))
    )
    (net (code "62") (name "/W25Q64_SCK") (class "Default")
      (node (ref "P5") (pin "15") (pinfunction "15_15") (pintype "passive"))
      (node (ref "U10") (pin "34") (pinfunction "PB13/SPI2_SCK/I2S2_CK/USART3_CTS/TIM1_CH1N/CAN2_TX/OTG_HS_ULPI_D6/ETH_RMII_TXD1/ETH_MII_TXD1/EVENTOUT/OTG_HS_VBUS_34") (pintype "bidirectional"))
      (node (ref "U14") (pin "6") (pinfunction "CLK_6") (pintype "passive"))
    )
    (net (code "63") (name "BAT+") (class "Default")
      (node (ref "BT1") (pin "1") (pinfunction "+_1") (pintype "passive"))
      (node (ref "P10") (pin "1") (pinfunction "1_1") (pintype "passive"))
      (node (ref "U6") (pin "3") (pinfunction "BAT_3") (pintype "passive"))
    )
    (net (code "64") (name "GND") (class "Default")
      (node (ref "B1") (pin "2") (pintype "passive"))
      (node (ref "BT1") (pin "2") (pinfunction "-_2") (pintype "passive"))
      (node (ref "C1") (pin "1") (pinfunction "1_1") (pintype "passive"))
      (node (ref "C100") (pin "2") (pinfunction "2_2") (pintype "passive"))
      (node (ref "C101") (pin "2") (pinfunction "2_2") (pintype "passive"))
      (node (ref "C102") (pin "2") (pinfunction "2_2") (pintype "passive"))
      (node (ref "C104") (pin "1") (pinfunction "1_1") (pintype "passive"))
      (node (ref "C105") (pin "1") (pinfunction "1_1") (pintype "passive"))
      (node (ref "C107") (pin "2") (pintype "passive"))
      (node (ref "C108") (pin "1") (pinfunction "1_1") (pintype "passive"))
      (node (ref "C109") (pin "1") (pinfunction "1_1") (pintype "passive"))
      (node (ref "C110") (pin "1") (pinfunction "1_1") (pintype "passive"))
      (node (ref "C111") (pin "1") (pinfunction "1_1") (pintype "passive"))
      (node (ref "C112") (pin "1") (pinfunction "1_1") (pintype "passive"))
      (node (ref "C114") (pin "1") (pinfunction "1_1") (pintype "passive"))
      (node (ref "C115") (pin "1") (pinfunction "1_1") (pintype "passive"))
      (node (ref "C116") (pin "1") (pinfunction "1_1") (pintype "passive"))
      (node (ref "C117") (pin "1") (pinfunction "1_1") (pintype "passive"))
      (node (ref "C12") (pin "2") (pinfunction "2_2") (pintype "passive"))
      (node (ref "C120") (pin "1") (pintype "passive"))
      (node (ref "C122") (pin "1") (pinfunction "1_1") (pintype "passive"))
      (node (ref "C123") (pin "1") (pinfunction "1_1") (pintype "passive"))
      (node (ref "C124") (pin "2") (pinfunction "2_2") (pintype "passive"))
      (node (ref "C126") (pin "1") (pinfunction "1_1") (pintype "passive"))
      (node (ref "C128") (pin "1") (pinfunction "1_1") (pintype "passive"))
      (node (ref "C13") (pin "1") (pinfunction "1_1") (pintype "passive"))
      (node (ref "C130") (pin "1") (pinfunction "1_1") (pintype "passive"))
      (node (ref "C131") (pin "1") (pinfunction "1_1") (pintype "passive"))
      (node (ref "C136") (pin "1") (pinfunction "1_1") (pintype "passive"))
      (node (ref "C14") (pin "2") (pinfunction "2_2") (pintype "passive"))
      (node (ref "C140") (pin "1") (pinfunction "1_1") (pintype "passive"))
      (node (ref "C15") (pin "1") (pinfunction "1_1") (pintype "passive"))
      (node (ref "C16") (pin "1") (pinfunction "1_1") (pintype "passive"))
      (node (ref "C17") (pin "1") (pinfunction "1_1") (pintype "passive"))
      (node (ref "C19") (pin "1") (pinfunction "1_1") (pintype "passive"))
      (node (ref "C2") (pin "1") (pinfunction "1_1") (pintype "passive"))
      (node (ref "C20") (pin "1") (pinfunction "1_1") (pintype "passive"))
      (node (ref "C23") (pin "1") (pintype "passive"))
      (node (ref "C24") (pin "1") (pinfunction "1_1") (pintype "passive"))
      (node (ref "C25") (pin "1") (pinfunction "1_1") (pintype "passive"))
      (node (ref "C26") (pin "1") (pinfunction "1_1") (pintype "passive"))
      (node (ref "C27") (pin "1") (pinfunction "1_1") (pintype "passive"))
      (node (ref "C28") (pin "1") (pinfunction "1_1") (pintype "passive"))
      (node (ref "C29") (pin "2") (pintype "passive"))
      (node (ref "C3") (pin "1") (pinfunction "1_1") (pintype "passive"))
      (node (ref "C30") (pin "2") (pintype "passive"))
      (node (ref "C31") (pin "2") (pinfunction "2_2") (pintype "passive"))
      (node (ref "C32") (pin "2") (pinfunction "2_2") (pintype "passive"))
      (node (ref "C33") (pin "1") (pinfunction "1_1") (pintype "passive"))
      (node (ref "C39") (pin "1") (pinfunction "1_1") (pintype "passive"))
      (node (ref "C4") (pin "2") (pinfunction "2_2") (pintype "passive"))
      (node (ref "C41") (pin "1") (pintype "passive"))
      (node (ref "C42") (pin "1") (pintype "passive"))
      (node (ref "C43") (pin "1") (pintype "passive"))
      (node (ref "C44") (pin "2") (pintype "passive"))
      (node (ref "C45") (pin "1") (pintype "passive"))
      (node (ref "C46") (pin "1") (pintype "passive"))
      (node (ref "C47") (pin "2") (pintype "passive"))
      (node (ref "C48") (pin "1") (pintype "passive"))
      (node (ref "C49") (pin "1") (pinfunction "1_1") (pintype "passive"))
      (node (ref "C5") (pin "2") (pinfunction "2_2") (pintype "passive"))
      (node (ref "C50") (pin "1") (pinfunction "1_1") (pintype "passive"))
      (node (ref "C51") (pin "2") (pintype "passive"))
      (node (ref "C53") (pin "2") (pintype "passive"))
      (node (ref "C54") (pin "1") (pintype "passive"))
      (node (ref "C55") (pin "2") (pintype "passive"))
      (node (ref "C57") (pin "2") (pintype "passive"))
      (node (ref "C58") (pin "2") (pintype "passive"))
      (node (ref "C59") (pin "2") (pintype "passive"))
      (node (ref "C6") (pin "2") (pinfunction "2_2") (pintype "passive"))
      (node (ref "C60") (pin "1") (pintype "passive"))
      (node (ref "C61") (pin "2") (pintype "passive"))
      (node (ref "C62") (pin "2") (pintype "passive"))
      (node (ref "C63") (pin "1") (pintype "passive"))
      (node (ref "C64") (pin "1") (pinfunction "1_1") (pintype "passive"))
      (node (ref "C65") (pin "1") (pinfunction "1_1") (pintype "passive"))
      (node (ref "C66") (pin "1") (pinfunction "1_1") (pintype "passive"))
      (node (ref "C67") (pin "1") (pinfunction "1_1") (pintype "passive"))
      (node (ref "C68") (pin "1") (pinfunction "1_1") (pintype "passive"))
      (node (ref "C69") (pin "2") (pinfunction "2_2") (pintype "passive"))
      (node (ref "C7") (pin "2") (pintype "passive"))
      (node (ref "C70") (pin "2") (pinfunction "2_2") (pintype "passive"))
      (node (ref "C71") (pin "2") (pinfunction "2_2") (pintype "passive"))
      (node (ref "C72") (pin "1") (pintype "passive"))
      (node (ref "C73") (pin "2") (pinfunction "2_2") (pintype "passive"))
      (node (ref "C77") (pin "1") (pinfunction "1_1") (pintype "passive"))
      (node (ref "C78") (pin "1") (pinfunction "1_1") (pintype "passive"))
      (node (ref "C79") (pin "1") (pintype "passive"))
      (node (ref "C8") (pin "1") (pinfunction "1_1") (pintype "passive"))
      (node (ref "C80") (pin "1") (pinfunction "1_1") (pintype "passive"))
      (node (ref "C84") (pin "2") (pintype "passive"))
      (node (ref "C85") (pin "1") (pinfunction "1_1") (pintype "passive"))
      (node (ref "C86") (pin "1") (pinfunction "1_1") (pintype "passive"))
      (node (ref "C88") (pin "1") (pinfunction "1_1") (pintype "passive"))
      (node (ref "C89") (pin "1") (pinfunction "1_1") (pintype "passive"))
      (node (ref "C90") (pin "1") (pinfunction "1_1") (pintype "passive"))
      (node (ref "C91") (pin "1") (pinfunction "1_1") (pintype "passive"))
      (node (ref "C92") (pin "1") (pinfunction "1_1") (pintype "passive"))
      (node (ref "C94") (pin "2") (pinfunction "2_2") (pintype "passive"))
      (node (ref "C95") (pin "2") (pinfunction "2_2") (pintype "passive"))
      (node (ref "C96") (pin "1") (pinfunction "1_1") (pintype "passive"))
      (node (ref "C97") (pin "1") (pintype "passive"))
      (node (ref "C98") (pin "2") (pintype "passive"))
      (node (ref "C99") (pin "1") (pinfunction "1_1") (pintype "passive"))
      (node (ref "D3") (pin "2") (pinfunction "K_2") (pintype "passive"))
      (node (ref "D4") (pin "2") (pinfunction "K_2") (pintype "passive"))
      (node (ref "D5") (pin "1") (pinfunction "A_1") (pintype "passive"))
      (node (ref "D6") (pin "1") (pinfunction "A_1") (pintype "passive"))
      (node (ref "J4") (pin "5") (pinfunction "GND_5") (pintype "passive"))
      (node (ref "L11") (pin "1") (pinfunction "1_1") (pintype "passive"))
      (node (ref "L25") (pin "1") (pinfunction "1_1") (pintype "passive"))
      (node (ref "L27") (pin "1") (pinfunction "1_1") (pintype "passive"))
      (node (ref "L28") (pin "1") (pinfunction "1_1") (pintype "passive"))
      (node (ref "LD1") (pin "2") (pinfunction "K_2") (pintype "passive"))
      (node (ref "MK1") (pin "2") (pinfunction "2_2") (pintype "passive"))
      (node (ref "P2") (pin "4") (pintype "passive"))
      (node (ref "P2") (pin "7") (pintype "passive"))
      (node (ref "P3") (pin "2") (pinfunction "Y_2") (pintype "passive"))
      (node (ref "P5") (pin "10") (pinfunction "10_10") (pintype "passive"))
      (node (ref "P5") (pin "3") (pinfunction "3_3") (pintype "passive"))
      (node (ref "P5") (pin "4") (pinfunction "4_4") (pintype "passive"))
      (node (ref "P5") (pin "9") (pinfunction "9_9") (pintype "passive"))
      (node (ref "P6") (pin "3") (pinfunction "3_3") (pintype "passive"))
      (node (ref "P8") (pin "2") (pinfunction "2_2") (pintype "passive"))
      (node (ref "P8") (pin "3") (pinfunction "3_3") (pintype "passive"))
      (node (ref "Q1") (pin "3") (pinfunction "S_3") (pintype "passive"))
      (node (ref "Q10") (pin "3") (pinfunction "S_3") (pintype "passive"))
      (node (ref "Q3") (pin "3") (pinfunction "E_3") (pintype "passive"))
      (node (ref "Q6") (pin "2") (pinfunction "E_2") (pintype "passive"))
      (node (ref "Q7") (pin "2") (pinfunction "2_2") (pintype "passive"))
      (node (ref "Q7") (pin "4") (pinfunction "4_4") (pintype "passive"))
      (node (ref "Q9") (pin "2") (pinfunction "E_2") (pintype "passive"))
      (node (ref "R12") (pin "1") (pintype "passive"))
      (node (ref "R19") (pin "1") (pinfunction "1_1") (pintype "passive"))
      (node (ref "R2") (pin "2") (pinfunction "2_2") (pintype "passive"))
      (node (ref "R20") (pin "1") (pinfunction "1_1") (pintype "passive"))
      (node (ref "R23") (pin "1") (pinfunction "1_1") (pintype "passive"))
      (node (ref "R4") (pin "1") (pinfunction "1_1") (pintype "passive"))
      (node (ref "R47") (pin "1") (pinfunction "1_1") (pintype "passive"))
      (node (ref "R49") (pin "2") (pinfunction "2_2") (pintype "passive"))
      (node (ref "S1") (pin "1") (pinfunction "1_1") (pintype "passive"))
      (node (ref "S2") (pin "2") (pinfunction "2_2") (pintype "passive"))
      (node (ref "U1") (pin "2") (pinfunction "GND_2") (pintype "passive"))
      (node (ref "U10") (pin "12") (pinfunction "VSSA_12") (pintype "power_in"))
      (node (ref "U10") (pin "18") (pinfunction "VSS_18") (pintype "power_in"))
      (node (ref "U10") (pin "63") (pinfunction "VSS_63") (pintype "power_in"))
      (node (ref "U12") (pin "3") (pinfunction "GND_3") (pintype "passive"))
      (node (ref "U13") (pin "2") (pinfunction "GND_2") (pintype "passive"))
      (node (ref "U14") (pin "4") (pinfunction "GND_4") (pintype "passive"))
      (node (ref "U4") (pin "15") (pinfunction "GND_15") (pintype "passive"))
      (node (ref "U4") (pin "23") (pinfunction "GND_23") (pintype "passive"))
      (node (ref "U4") (pin "26") (pinfunction "GND_26") (pintype "passive"))
      (node (ref "U4") (pin "29") (pinfunction "GND_29") (pintype "passive"))
      (node (ref "U5") (pin "2") (pinfunction "GND_2") (pintype "passive"))
      (node (ref "U6") (pin "2") (pinfunction "GND_2") (pintype "passive"))
      (node (ref "U7") (pin "2") (pinfunction "GND_2") (pintype "passive"))
      (node (ref "U8") (pin "33") (pinfunction "GND_33") (pintype "passive"))
      (node (ref "U8") (pin "7") (pinfunction "MODE_7") (pintype "passive"))
      (node (ref "U8") (pin "8") (pinfunction "SENB_8") (pintype "passive"))
      (node (ref "U9") (pin "15") (pinfunction "MODE_15") (pintype "passive"))
      (node (ref "U9") (pin "18") (pinfunction "SPKGND_18") (pintype "passive"))
      (node (ref "U9") (pin "25") (pinfunction "GND_25") (pintype "passive"))
      (node (ref "U9") (pin "3") (pinfunction "AGND_3") (pintype "passive"))
      (node (ref "U9") (pin "6") (pinfunction "DGND_6") (pintype "passive"))
    )
    (net (code "65") (name "LNA_En") (class "Default")
      (node (ref "R6") (pin "2") (pinfunction "2_2") (pintype "passive"))
      (node (ref "U10") (pin "54") (pinfunction "PD2/TIM3_ETR/UART5_RX/SDIO_CMD/DCMI_D11/EVENTOUT_54") (pintype "bidirectional"))
    )
    (net (code "66") (name "LNA_Trans_En") (class "Default")
      (node (ref "C29") (pin "1") (pintype "passive"))
      (node (ref "C30") (pin "1") (pintype "passive"))
      (node (ref "Q5") (pin "1") (pinfunction "B_1") (pintype "passive"))
      (node (ref "Q6") (pin "1") (pinfunction "B_1") (pintype "passive"))
      (node (ref "U10") (pin "25") (pinfunction "PC5/ETH_RMII_RX_D1/ETH_MII_RX_D1/EVENTOUT/ADC12_IN15_25") (pintype "bidirectional"))
    )
    (net (code "67") (name "Net-(B1-Pad1)") (class "Default")
      (node (ref "B1") (pin "1") (pintype "passive"))
      (node (ref "Q4") (pin "2") (pinfunction "2_2") (pintype "passive"))
    )
    (net (code "68") (name "Net-(C10-Pad1)") (class "Default")
      (node (ref "C10") (pin "1") (pinfunction "1_1") (pintype "passive"))
      (node (ref "C32") (pin "1") (pinfunction "1_1") (pintype "passive"))
      (node (ref "L10") (pin "1") (pinfunction "1_1") (pintype "passive"))
      (node (ref "L5") (pin "1") (pinfunction "1_1") (pintype "passive"))
      (node (ref "Q7") (pin "1") (pinfunction "1_1") (pintype "passive"))
    )
    (net (code "69") (name "Net-(C10-Pad2)") (class "Default")
      (node (ref "C10") (pin "2") (pinfunction "2_2") (pintype "passive"))
      (node (ref "C74") (pin "1") (pinfunction "1_1") (pintype "passive"))
      (node (ref "L10") (pin "2") (pinfunction "2_2") (pintype "passive"))
    )
    (net (code "70") (name "Net-(C11-Pad1)") (class "Default")
      (node (ref "C11") (pin "1") (pinfunction "1_1") (pintype "passive"))
      (node (ref "C81") (pin "1") (pinfunction "1_1") (pintype "passive"))
      (node (ref "L11") (pin "2") (pinfunction "2_2") (pintype "passive"))
    )
    (net (code "71") (name "Net-(C18-Pad2)") (class "Default")
      (node (ref "C18") (pin "2") (pinfunction "2_2") (pintype "passive"))
      (node (ref "C19") (pin "2") (pinfunction "2_2") (pintype "passive"))
      (node (ref "L8") (pin "2") (pinfunction "2_2") (pintype "passive"))
    )
    (net (code "72") (name "Net-(C73-Pad1)") (class "Default")
      (node (ref "C73") (pin "1") (pinfunction "1_1") (pintype "passive"))
      (node (ref "C9") (pin "2") (pinfunction "2_2") (pintype "passive"))
      (node (ref "L4") (pin "1") (pinfunction "1_1") (pintype "passive"))
      (node (ref "L7") (pin "2") (pinfunction "2_2") (pintype "passive"))
      (node (ref "Q7") (pin "3") (pinfunction "3_3") (pintype "passive"))
    )
    (net (code "73") (name "Net-(C87-Pad2)") (class "Default")
      (node (ref "C87") (pin "2") (pinfunction "2_2") (pintype "passive"))
      (node (ref "C90") (pin "2") (pinfunction "2_2") (pintype "passive"))
      (node (ref "L14") (pin "2") (pinfunction "2_2") (pintype "passive"))
    )
    (net (code "74") (name "Net-(C108-Pad2)") (class "Default")
      (node (ref "C108") (pin "2") (pinfunction "2_2") (pintype "passive"))
      (node (ref "C109") (pin "2") (pinfunction "2_2") (pintype "passive"))
      (node (ref "C110") (pin "2") (pinfunction "2_2") (pintype "passive"))
      (node (ref "C139") (pin "1") (pinfunction "1_1") (pintype "passive"))
      (node (ref "L26") (pin "1") (pinfunction "1_1") (pintype "passive"))
    )
    (net (code "75") (name "Net-(C121-Pad2)") (class "Default")
      (node (ref "C121") (pin "2") (pinfunction "2_2") (pintype "passive"))
      (node (ref "C122") (pin "2") (pinfunction "2_2") (pintype "passive"))
      (node (ref "C125") (pin "2") (pinfunction "2_2") (pintype "passive"))
      (node (ref "C136") (pin "2") (pinfunction "2_2") (pintype "passive"))
      (node (ref "L20") (pin "1") (pinfunction "1_1") (pintype "passive"))
      (node (ref "R51") (pin "2") (pinfunction "2_2") (pintype "passive"))
    )
    (net (code "76") (name "Net-(C126-Pad2)") (class "Default")
      (node (ref "C126") (pin "2") (pinfunction "2_2") (pintype "passive"))
      (node (ref "R52") (pin "1") (pinfunction "1_1") (pintype "passive"))
    )
    (net (code "77") (name "Net-(C129-Pad1)") (class "Default")
      (node (ref "C129") (pin "1") (pinfunction "1_1") (pintype "passive"))
      (node (ref "L24") (pin "1") (pinfunction "1_1") (pintype "passive"))
    )
    (net (code "78") (name "Net-(C132-Pad2)") (class "Default")
      (node (ref "C132") (pin "2") (pinfunction "2_2") (pintype "passive"))
      (node (ref "C9") (pin "1") (pinfunction "1_1") (pintype "passive"))
      (node (ref "L7") (pin "1") (pinfunction "1_1") (pintype "passive"))
    )
    (net (code "79") (name "Net-(C135-Pad1)") (class "Default")
      (node (ref "C135") (pin "1") (pinfunction "1_1") (pintype "passive"))
      (node (ref "C82") (pin "1") (pinfunction "1_1") (pintype "passive"))
      (node (ref "L28") (pin "2") (pinfunction "2_2") (pintype "passive"))
    )
    (net (code "80") (name "Net-(D1-A)") (class "Default")
      (node (ref "D1") (pin "1") (pinfunction "A_1") (pintype "passive"))
      (node (ref "L2") (pin "2") (pinfunction "2_2") (pintype "passive"))
      (node (ref "U13") (pin "1") (pinfunction "SW_1") (pintype "passive"))
    )
    (net (code "81") (name "Net-(D2-A)") (class "Default")
      (node (ref "C75") (pin "2") (pintype "passive"))
      (node (ref "D2") (pin "1") (pinfunction "A_1") (pintype "passive"))
      (node (ref "L15") (pin "2") (pinfunction "2_2") (pintype "passive"))
    )
    (net (code "82") (name "Net-(D2-K)") (class "Default")
      (node (ref "C76") (pin "1") (pintype "passive"))
      (node (ref "D2") (pin "2") (pinfunction "K_2") (pintype "passive"))
      (node (ref "L16") (pin "2") (pinfunction "2_2") (pintype "passive"))
    )
    (net (code "83") (name "Net-(D3-A)") (class "Default")
      (node (ref "C74") (pin "2") (pinfunction "2_2") (pintype "passive"))
      (node (ref "C75") (pin "1") (pintype "passive"))
      (node (ref "D3") (pin "1") (pinfunction "A_1") (pintype "passive"))
      (node (ref "D4") (pin "1") (pinfunction "A_1") (pintype "passive"))
      (node (ref "L17") (pin "2") (pinfunction "2_2") (pintype "passive"))
    )
    (net (code "84") (name "Net-(D6-K)") (class "Default")
      (node (ref "C127") (pin "2") (pintype "passive"))
      (node (ref "C76") (pin "2") (pintype "passive"))
      (node (ref "D6") (pin "2") (pinfunction "K_2") (pintype "passive"))
      (node (ref "P3") (pin "1") (pinfunction "X_1") (pintype "passive"))
    )
    (net (code "85") (name "Net-(D7-A)") (class "Default")
      (node (ref "C134") (pin "2") (pintype "passive"))
      (node (ref "D7") (pin "2") (pinfunction "A_2") (pintype "passive"))
      (node (ref "L21") (pin "2") (pinfunction "2_2") (pintype "passive"))
    )
    (net (code "86") (name "Net-(D7-K)") (class "Default")
      (node (ref "C127") (pin "1") (pintype "passive"))
      (node (ref "D7") (pin "1") (pinfunction "K_1") (pintype "passive"))
      (node (ref "L23") (pin "2") (pinfunction "2_2") (pintype "passive"))
    )
    (net (code "87") (name "Net-(J4-D+)") (class "Default")
      (node (ref "J4") (pin "3") (pinfunction "D+_3") (pintype "passive"))
      (node (ref "R15") (pin "2") (pinfunction "2_2") (pintype "passive"))
    )
    (net (code "88") (name "Net-(J4-D-)") (class "Default")
      (node (ref "J4") (pin "2") (pinfunction "D-_2") (pintype "passive"))
      (node (ref "R14") (pin "2") (pinfunction "2_2") (pintype "passive"))
    )
    (net (code "89") (name "Net-(J4-NCC)") (class "Default")
      (node (ref "J4") (pin "4") (pinfunction "NCC_4") (pintype "passive"))
      (node (ref "R16") (pin "2") (pinfunction "2_2") (pintype "passive"))
    )
    (net (code "90") (name "Net-(L4-Pad2)") (class "Default")
      (node (ref "L4") (pin "2") (pinfunction "2_2") (pintype "passive"))
      (node (ref "R7") (pin "1") (pinfunction "1_1") (pintype "passive"))
    )
    (net (code "91") (name "Net-(L5-Pad2)") (class "Default")
      (node (ref "L5") (pin "2") (pinfunction "2_2") (pintype "passive"))
      (node (ref "R8") (pin "1") (pinfunction "1_1") (pintype "passive"))
    )
    (net (code "92") (name "Net-(L6-Pad2)") (class "Default")
      (node (ref "L6") (pin "2") (pinfunction "2_2") (pintype "passive"))
      (node (ref "R32") (pin "2") (pinfunction "2_2") (pintype "passive"))
      (node (ref "R47") (pin "2") (pinfunction "2_2") (pintype "passive"))
    )
    (net (code "93") (name "Net-(L16-Pad1)") (class "Default")
      (node (ref "L16") (pin "1") (pinfunction "1_1") (pintype "passive"))
      (node (ref "R21") (pin "1") (pinfunction "1_1") (pintype "passive"))
    )
    (net (code "94") (name "Net-(L17-Pad1)") (class "Default")
      (node (ref "L17") (pin "1") (pinfunction "1_1") (pintype "passive"))
      (node (ref "R24") (pin "1") (pinfunction "1_1") (pintype "passive"))
    )
    (net (code "95") (name "Net-(L20-Pad2)") (class "Default")
      (node (ref "L20") (pin "2") (pinfunction "2_2") (pintype "passive"))
      (node (ref "R48") (pin "2") (pinfunction "2_2") (pintype "passive"))
      (node (ref "R49") (pin "1") (pinfunction "1_1") (pintype "passive"))
    )
    (net (code "96") (name "Net-(L23-Pad1)") (class "Default")
      (node (ref "L23") (pin "1") (pinfunction "1_1") (pintype "passive"))
      (node (ref "R50") (pin "1") (pinfunction "1_1") (pintype "passive"))
    )
    (net (code "97") (name "Net-(LD1-A)") (class "Default")
      (node (ref "LD1") (pin "1") (pinfunction "A_1") (pintype "passive"))
      (node (ref "R1") (pin "1") (pintype "passive"))
    )
    (net (code "98") (name "Net-(LD2-A)") (class "Default")
      (node (ref "LD2") (pin "1") (pinfunction "A_1") (pintype "passive"))
      (node (ref "R28") (pin "1") (pintype "passive"))
    )
    (net (code "99") (name "Net-(P4-Pad2)") (class "Default")
      (node (ref "P4") (pin "2") (pinfunction "2_2") (pintype "passive"))
      (node (ref "R18") (pin "1") (pinfunction "1_1") (pintype "passive"))
    )
    (net (code "100") (name "Net-(Q1-D)") (class "Default")
      (node (ref "C104") (pin "2") (pinfunction "2_2") (pintype "passive"))
      (node (ref "C105") (pin "2") (pinfunction "2_2") (pintype "passive"))
      (node (ref "C121") (pin "1") (pinfunction "1_1") (pintype "passive"))
      (node (ref "L18") (pin "1") (pinfunction "1_1") (pintype "passive"))
      (node (ref "Q1") (pin "1") (pinfunction "D_1") (pintype "passive"))
    )
    (net (code "101") (name "Net-(Q1-G)") (class "Default")
      (node (ref "C111") (pin "2") (pinfunction "2_2") (pintype "passive"))
      (node (ref "C112") (pin "2") (pinfunction "2_2") (pintype "passive"))
      (node (ref "L26") (pin "2") (pinfunction "2_2") (pintype "passive"))
      (node (ref "L6") (pin "1") (pinfunction "1_1") (pintype "passive"))
      (node (ref "Q1") (pin "2") (pinfunction "G_2") (pintype "passive"))
      (node (ref "R52") (pin "2") (pinfunction "2_2") (pintype "passive"))
    )
    (net (code "102") (name "Net-(Q2-D)") (class "Default")
      (node (ref "C8") (pin "2") (pinfunction "2_2") (pintype "passive"))
      (node (ref "Q2") (pin "2") (pinfunction "D_2") (pintype "passive"))
      (node (ref "R8") (pin "2") (pinfunction "2_2") (pintype "passive"))
    )
    (net (code "103") (name "Net-(Q2-G)") (class "Default")
      (node (ref "Q2") (pin "1") (pinfunction "G_1") (pintype "passive"))
      (node (ref "R6") (pin "1") (pinfunction "1_1") (pintype "passive"))
    )
    (net (code "104") (name "Net-(Q3-B)") (class "Default")
      (node (ref "C130") (pin "2") (pinfunction "2_2") (pintype "passive"))
      (node (ref "L24") (pin "2") (pinfunction "2_2") (pintype "passive"))
      (node (ref "Q3") (pin "2") (pinfunction "B_2") (pintype "passive"))
      (node (ref "R35") (pin "2") (pinfunction "2_2") (pintype "passive"))
    )
    (net (code "105") (name "Net-(Q3-C)") (class "Default")
      (node (ref "C128") (pin "2") (pinfunction "2_2") (pintype "passive"))
      (node (ref "L14") (pin "1") (pinfunction "1_1") (pintype "passive"))
      (node (ref "L9") (pin "1") (pinfunction "1_1") (pintype "passive"))
      (node (ref "Q3") (pin "1") (pinfunction "C_1") (pintype "passive"))
    )
    (net (code "106") (name "Net-(Q5-E)") (class "Default")
      (node (ref "Q5") (pin "2") (pinfunction "E_2") (pintype "passive"))
      (node (ref "R24") (pin "2") (pinfunction "2_2") (pintype "passive"))
    )
    (net (code "107") (name "Net-(Q6-C)") (class "Default")
      (node (ref "Q6") (pin "3") (pinfunction "C_3") (pintype "passive"))
      (node (ref "R21") (pin "2") (pinfunction "2_2") (pintype "passive"))
    )
    (net (code "108") (name "Net-(Q8-D)") (class "Default")
      (node (ref "C77") (pin "2") (pinfunction "2_2") (pintype "passive"))
      (node (ref "C78") (pin "2") (pinfunction "2_2") (pintype "passive"))
      (node (ref "C91") (pin "2") (pinfunction "2_2") (pintype "passive"))
      (node (ref "Q8") (pin "2") (pinfunction "D_2") (pintype "passive"))
      (node (ref "R32") (pin "1") (pinfunction "1_1") (pintype "passive"))
      (node (ref "R48") (pin "1") (pinfunction "1_1") (pintype "passive"))
    )
    (net (code "109") (name "Net-(Q8-G)") (class "Default")
      (node (ref "Q8") (pin "1") (pinfunction "G_1") (pintype "passive"))
      (node (ref "R27") (pin "1") (pinfunction "1_1") (pintype "passive"))
    )
    (net (code "110") (name "Net-(Q9-C)") (class "Default")
      (node (ref "Q9") (pin "3") (pinfunction "C_3") (pintype "passive"))
      (node (ref "R50") (pin "2") (pinfunction "2_2") (pintype "passive"))
    )
    (net (code "111") (name "Net-(Q10-D)") (class "Default")
      (node (ref "C114") (pin "2") (pinfunction "2_2") (pintype "passive"))
      (node (ref "C115") (pin "2") (pinfunction "2_2") (pintype "passive"))
      (node (ref "C116") (pin "2") (pinfunction "2_2") (pintype "passive"))
      (node (ref "C117") (pin "2") (pinfunction "2_2") (pintype "passive"))
      (node (ref "C134") (pin "1") (pintype "passive"))
      (node (ref "C140") (pin "2") (pinfunction "2_2") (pintype "passive"))
      (node (ref "L19") (pin "1") (pinfunction "1_1") (pintype "passive"))
      (node (ref "Q10") (pin "1") (pinfunction "D_1") (pintype "passive"))
    )
    (net (code "112") (name "Net-(Q10-G)") (class "Default")
      (node (ref "C125") (pin "1") (pinfunction "1_1") (pintype "passive"))
      (node (ref "Q10") (pin "2") (pinfunction "G_2") (pintype "passive"))
      (node (ref "R51") (pin "1") (pinfunction "1_1") (pintype "passive"))
    )
    (net (code "113") (name "Net-(U1-BP)") (class "Default")
      (node (ref "C6") (pin "1") (pinfunction "1_1") (pintype "passive"))
      (node (ref "U1") (pin "4") (pinfunction "BP_4") (pintype "passive"))
    )
    (net (code "114") (name "Net-(U4-NRESET)") (class "Default")
      (node (ref "C15") (pin "2") (pinfunction "2_2") (pintype "passive"))
      (node (ref "R5") (pin "1") (pinfunction "1_1") (pintype "passive"))
      (node (ref "U4") (pin "7") (pinfunction "NRESET_7") (pintype "passive"))
    )
    (net (code "115") (name "Net-(U4-PA_BOOST)") (class "Default")
      (node (ref "L1") (pin "2") (pinfunction "2_2") (pintype "passive"))
      (node (ref "L8") (pin "1") (pinfunction "1_1") (pintype "passive"))
      (node (ref "U4") (pin "27") (pinfunction "PA_BOOST_27") (pintype "passive"))
    )
    (net (code "116") (name "Net-(U4-RFI_LF)") (class "Default")
      (node (ref "C11") (pin "2") (pinfunction "2_2") (pintype "passive"))
      (node (ref "L25") (pin "2") (pinfunction "2_2") (pintype "passive"))
      (node (ref "U4") (pin "1") (pinfunction "RFI_LF_1") (pintype "passive"))
    )
    (net (code "117") (name "Net-(U4-VR_ANA)") (class "Default")
      (node (ref "C16") (pin "2") (pinfunction "2_2") (pintype "passive"))
      (node (ref "U4") (pin "2") (pinfunction "VR_ANA_2") (pintype "passive"))
    )
    (net (code "118") (name "Net-(U4-VR_DIG)") (class "Default")
      (node (ref "C17") (pin "2") (pinfunction "2_2") (pintype "passive"))
      (node (ref "U4") (pin "4") (pinfunction "VR_DIG_4") (pintype "passive"))
    )
    (net (code "119") (name "Net-(U4-VR_PA)") (class "Default")
      (node (ref "C24") (pin "2") (pinfunction "2_2") (pintype "passive"))
      (node (ref "C25") (pin "2") (pinfunction "2_2") (pintype "passive"))
      (node (ref "L1") (pin "1") (pinfunction "1_1") (pintype "passive"))
      (node (ref "U4") (pin "25") (pinfunction "VR_PA_25") (pintype "passive"))
    )
    (net (code "120") (name "Net-(U4-XTA)") (class "Default")
      (node (ref "C13") (pin "2") (pinfunction "2_2") (pintype "passive"))
      (node (ref "U4") (pin "5") (pinfunction "XTA_5") (pintype "passive"))
      (node (ref "Y1") (pin "2") (pinfunction "OSC2_2") (pintype "passive"))
    )
    (net (code "121") (name "Net-(U4-XTB)") (class "Default")
      (node (ref "C12") (pin "1") (pinfunction "1_1") (pintype "passive"))
      (node (ref "U4") (pin "6") (pinfunction "XTB_6") (pintype "passive"))
      (node (ref "Y1") (pin "1") (pinfunction "OSC1_1") (pintype "passive"))
    )
    (net (code "122") (name "Net-(U5-RF1)") (class "Default")
      (node (ref "C81") (pin "2") (pinfunction "2_2") (pintype "passive"))
      (node (ref "U5") (pin "1") (pinfunction "RF1_1") (pintype "passive"))
    )
    (net (code "123") (name "Net-(U5-RF2)") (class "Default")
      (node (ref "C82") (pin "2") (pinfunction "2_2") (pintype "passive"))
      (node (ref "U5") (pin "3") (pinfunction "RF2_3") (pintype "passive"))
    )
    (net (code "124") (name "Net-(U5-RFC)") (class "Default")
      (node (ref "C132") (pin "1") (pinfunction "1_1") (pintype "passive"))
      (node (ref "U5") (pin "5") (pinfunction "RFC_5") (pintype "passive"))
    )
    (net (code "125") (name "Net-(U6-PROG)") (class "Default")
      (node (ref "R2") (pin "1") (pinfunction "1_1") (pintype "passive"))
      (node (ref "U6") (pin "5") (pinfunction "PROG_5") (pintype "passive"))
    )
    (net (code "126") (name "Net-(U7-RF1)") (class "Default")
      (node (ref "C18") (pin "1") (pinfunction "1_1") (pintype "passive"))
      (node (ref "U7") (pin "1") (pinfunction "RF1_1") (pintype "passive"))
    )
    (net (code "127") (name "Net-(U7-RF2)") (class "Default")
      (node (ref "C87") (pin "1") (pinfunction "1_1") (pintype "passive"))
      (node (ref "U7") (pin "3") (pinfunction "RF2_3") (pintype "passive"))
    )
    (net (code "128") (name "Net-(U7-RFC)") (class "Default")
      (node (ref "C139") (pin "2") (pinfunction "2_2") (pintype "passive"))
      (node (ref "U7") (pin "5") (pinfunction "RFC_5") (pintype "passive"))
    )
    (net (code "129") (name "Net-(U8-CC)") (class "Default")
      (node (ref "C54") (pin "2") (pintype "passive"))
      (node (ref "U8") (pin "12") (pinfunction "CC_12") (pintype "passive"))
    )
    (net (code "130") (name "Net-(U8-PABIAS)") (class "Default")
      (node (ref "C86") (pin "2") (pinfunction "2_2") (pintype "passive"))
      (node (ref "C89") (pin "2") (pinfunction "2_2") (pintype "passive"))
      (node (ref "R35") (pin "1") (pinfunction "1_1") (pintype "passive"))
      (node (ref "U8") (pin "22") (pinfunction "PABIAS_22") (pintype "passive"))
    )
    (net (code "131") (name "Net-(U8-RF_IN)") (class "Default")
      (node (ref "C135") (pin "2") (pinfunction "2_2") (pintype "passive"))
      (node (ref "L27") (pin "2") (pinfunction "2_2") (pintype "passive"))
      (node (ref "U8") (pin "15") (pinfunction "RF_IN_15") (pintype "passive"))
    )
    (net (code "132") (name "Net-(U8-RF_OUT)") (class "Default")
      (node (ref "C129") (pin "2") (pinfunction "2_2") (pintype "passive"))
      (node (ref "C131") (pin "2") (pinfunction "2_2") (pintype "passive"))
      (node (ref "U8") (pin "18") (pinfunction "RF_OUT_18") (pintype "passive"))
    )
    (net (code "133") (name "Net-(U8-XTAL1)") (class "Default")
      (node (ref "C49") (pin "2") (pinfunction "2_2") (pintype "passive"))
      (node (ref "U8") (pin "5") (pinfunction "XTAL1_5") (pintype "passive"))
      (node (ref "Y2") (pin "1") (pinfunction "OSC1_1") (pintype "passive"))
    )
    (net (code "134") (name "Net-(U8-XTAL2)") (class "Default")
      (node (ref "C50") (pin "2") (pinfunction "2_2") (pintype "passive"))
      (node (ref "U8") (pin "6") (pinfunction "XTAL2_6") (pintype "passive"))
      (node (ref "Y2") (pin "2") (pinfunction "OSC2_2") (pintype "passive"))
    )
    (net (code "135") (name "Net-(U9-MICBIAS)") (class "Default")
      (node (ref "C62") (pin "1") (pintype "passive"))
      (node (ref "R11") (pin "2") (pintype "passive"))
      (node (ref "U9") (pin "1") (pinfunction "MICBIAS_1") (pintype "passive"))
    )
    (net (code "136") (name "Net-(U9-MICN)") (class "Default")
      (node (ref "C56") (pin "2") (pintype "passive"))
      (node (ref "U9") (pin "23") (pinfunction "MICN_23") (pintype "passive"))
    )
    (net (code "137") (name "Net-(U9-MICP)") (class "Default")
      (node (ref "C52") (pin "1") (pintype "passive"))
      (node (ref "U9") (pin "24") (pinfunction "MICP_24") (pintype "passive"))
    )
    (net (code "138") (name "Net-(U9-MONOOUT)") (class "Default")
      (node (ref "C40") (pin "2") (pintype "passive"))
      (node (ref "U9") (pin "16") (pinfunction "MONOOUT_16") (pintype "passive"))
    )
    (net (code "139") (name "Net-(U9-SPKOUTN)") (class "Default")
      (node (ref "C113") (pin "1") (pinfunction "1_1") (pintype "passive"))
      (node (ref "U9") (pin "19") (pinfunction "SPKOUTN_19") (pintype "passive"))
    )
    (net (code "140") (name "Net-(U9-SPKOUTP)") (class "Default")
      (node (ref "C83") (pin "1") (pinfunction "1_1") (pintype "passive"))
      (node (ref "U9") (pin "17") (pinfunction "SPKOUTP_17") (pintype "passive"))
    )
    (net (code "141") (name "Net-(U9-VMID)") (class "Default")
      (node (ref "C51") (pin "1") (pintype "passive"))
      (node (ref "U9") (pin "22") (pinfunction "VMID_22") (pintype "passive"))
    )
    (net (code "142") (name "Net-(U10C-VCAP_1)") (class "Default")
      (node (ref "C96") (pin "2") (pinfunction "2_2") (pintype "passive"))
      (node (ref "U10") (pin "31") (pinfunction "VCAP_1_31") (pintype "power_in"))
    )
    (net (code "143") (name "Net-(U10C-VCAP_2)") (class "Default")
      (node (ref "C92") (pin "2") (pinfunction "2_2") (pintype "passive"))
      (node (ref "U10") (pin "47") (pinfunction "VCAP_2_47") (pintype "power_in"))
    )
    (net (code "144") (name "Net-(U13-FB)") (class "Default")
      (node (ref "R3") (pin "1") (pinfunction "1_1") (pintype "passive"))
      (node (ref "R4") (pin "2") (pinfunction "2_2") (pintype "passive"))
      (node (ref "U13") (pin "3") (pinfunction "FB_3") (pintype "passive"))
    )
    (net (code "145") (name "PA_En") (class "Default")
      (node (ref "R27") (pin "2") (pinfunction "2_2") (pintype "passive"))
      (node (ref "U10") (pin "56") (pinfunction "PB4(NJTRST)/NJTRST/SPI3_MISO/TIM3_CH1/SPI1_MISO/I2S3ext_SD/EVENTOUT_56") (pintype "bidirectional"))
    )
    (net (code "146") (name "PA_Trans_En") (class "Default")
      (node (ref "C107") (pin "1") (pintype "passive"))
      (node (ref "Q9") (pin "1") (pinfunction "B_1") (pintype "passive"))
      (node (ref "U10") (pin "55") (pinfunction "PB3(JTDO/TRACESWO)/JTDO/TRACESWO/SPI3_SCK/I2S3_CK/TIM2_CH2/SPI1_SCK/EVENTOUT_55") (pintype "bidirectional"))
    )
    (net (code "147") (name "VBAT") (class "Default")
      (node (ref "C1") (pin "2") (pinfunction "2_2") (pintype "passive"))
      (node (ref "C120") (pin "2") (pintype "passive"))
      (node (ref "C123") (pin "2") (pinfunction "2_2") (pintype "passive"))
      (node (ref "C124") (pin "1") (pinfunction "1_1") (pintype "passive"))
      (node (ref "C23") (pin "2") (pintype "passive"))
      (node (ref "C3") (pin "2") (pinfunction "2_2") (pintype "passive"))
      (node (ref "C80") (pin "2") (pinfunction "2_2") (pintype "passive"))
      (node (ref "C85") (pin "2") (pinfunction "2_2") (pintype "passive"))
      (node (ref "C88") (pin "2") (pinfunction "2_2") (pintype "passive"))
      (node (ref "C95") (pin "1") (pinfunction "1_1") (pintype "passive"))
      (node (ref "L15") (pin "1") (pinfunction "1_1") (pintype "passive"))
      (node (ref "L18") (pin "2") (pinfunction "2_2") (pintype "passive"))
      (node (ref "L19") (pin "2") (pinfunction "2_2") (pintype "passive"))
      (node (ref "L2") (pin "1") (pinfunction "1_1") (pintype "passive"))
      (node (ref "L21") (pin "1") (pinfunction "1_1") (pintype "passive"))
      (node (ref "L9") (pin "2") (pinfunction "2_2") (pintype "passive"))
      (node (ref "P10") (pin "2") (pinfunction "2_2") (pintype "passive"))
      (node (ref "Q5") (pin "3") (pinfunction "C_3") (pintype "passive"))
      (node (ref "R22") (pin "2") (pinfunction "2_2") (pintype "passive"))
      (node (ref "U1") (pin "1") (pinfunction "VIN_1") (pintype "passive"))
      (node (ref "U1") (pin "3") (pinfunction "EN_3") (pintype "passive"))
      (node (ref "U13") (pin "5") (pinfunction "IN_5") (pintype "passive"))
    )
    (net (code "148") (name "VDDA") (class "Default")
      (node (ref "C72") (pin "2") (pintype "passive"))
      (node (ref "L3") (pin "2") (pinfunction "2_2") (pintype "passive"))
      (node (ref "U10") (pin "13") (pinfunction "VDDA_13") (pintype "power_in"))
    )
    (net (code "149") (name "VUSB") (class "Default")
      (node (ref "J4") (pin "1") (pinfunction "VDD_1") (pintype "passive"))
      (node (ref "P6") (pin "1") (pinfunction "1_1") (pintype "passive"))
      (node (ref "P8") (pin "1") (pinfunction "1_1") (pintype "passive"))
      (node (ref "U6") (pin "4") (pinfunction "VCC_4") (pintype "passive"))
    )
    (net (code "150") (name "unconnected-(U4-RFI_HF-Pad21)") (class "Default")
      (node (ref "U4") (pin "21") (pinfunction "RFI_HF_21") (pintype "passive+no_connect"))
    )
    (net (code "151") (name "unconnected-(U4-RFO_HF-Pad22)") (class "Default")
      (node (ref "U4") (pin "22") (pinfunction "RFO_HF_22") (pintype "passive+no_connect"))
    )
    (net (code "152") (name "unconnected-(U4-RFO_LF-Pad28)") (class "Default")
      (node (ref "U4") (pin "28") (pinfunction "RFO_LF_28") (pintype "passive+no_connect"))
    )
    (net (code "153") (name "unconnected-(U4-RXTX{slash}RFMOD-Pad20)") (class "Default")
      (node (ref "U4") (pin "20") (pinfunction "RXTX/RFMOD_20") (pintype "passive+no_connect"))
    )
    (net (code "154") (name "unconnected-(U8-NC-Pad10)") (class "Default")
      (node (ref "U8") (pin "10") (pinfunction "NC_10") (pintype "passive+no_connect"))
    )
    (net (code "155") (name "unconnected-(U8-NC-Pad14)") (class "Default")
      (node (ref "U8") (pin "14") (pinfunction "NC_14") (pintype "passive+no_connect"))
    )
    (net (code "156") (name "unconnected-(U8-NC-Pad17)") (class "Default")
      (node (ref "U8") (pin "17") (pinfunction "NC_17") (pintype "passive+no_connect"))
    )
    (net (code "157") (name "unconnected-(U8-NC-Pad19)") (class "Default")
      (node (ref "U8") (pin "19") (pinfunction "NC_19") (pintype "passive+no_connect"))
    )
    (net (code "158") (name "unconnected-(U8-NC-Pad20)") (class "Default")
      (node (ref "U8") (pin "20") (pinfunction "NC_20") (pintype "passive+no_connect"))
    )
    (net (code "159") (name "unconnected-(U9-AUX-Pad21)") (class "Default")
      (node (ref "U9") (pin "21") (pinfunction "AUX_21") (pintype "passive+no_connect"))
    )
    (net (code "160") (name "unconnected-(U9-CSB{slash}GPIO-Pad12)") (class "Default")
      (node (ref "U9") (pin "12") (pinfunction "CSB/GPIO_12") (pintype "passive+no_connect"))
    )
    (net (code "161") (name "unconnected-(U13-NC-Pad6)") (class "Default")
      (node (ref "U13") (pin "6") (pinfunction "NC_6") (pintype "passive"))
    )
  )
)
